# Calliope_mini_rev1_3.net
KiCad netlist of a schematic drawn in EAGLE
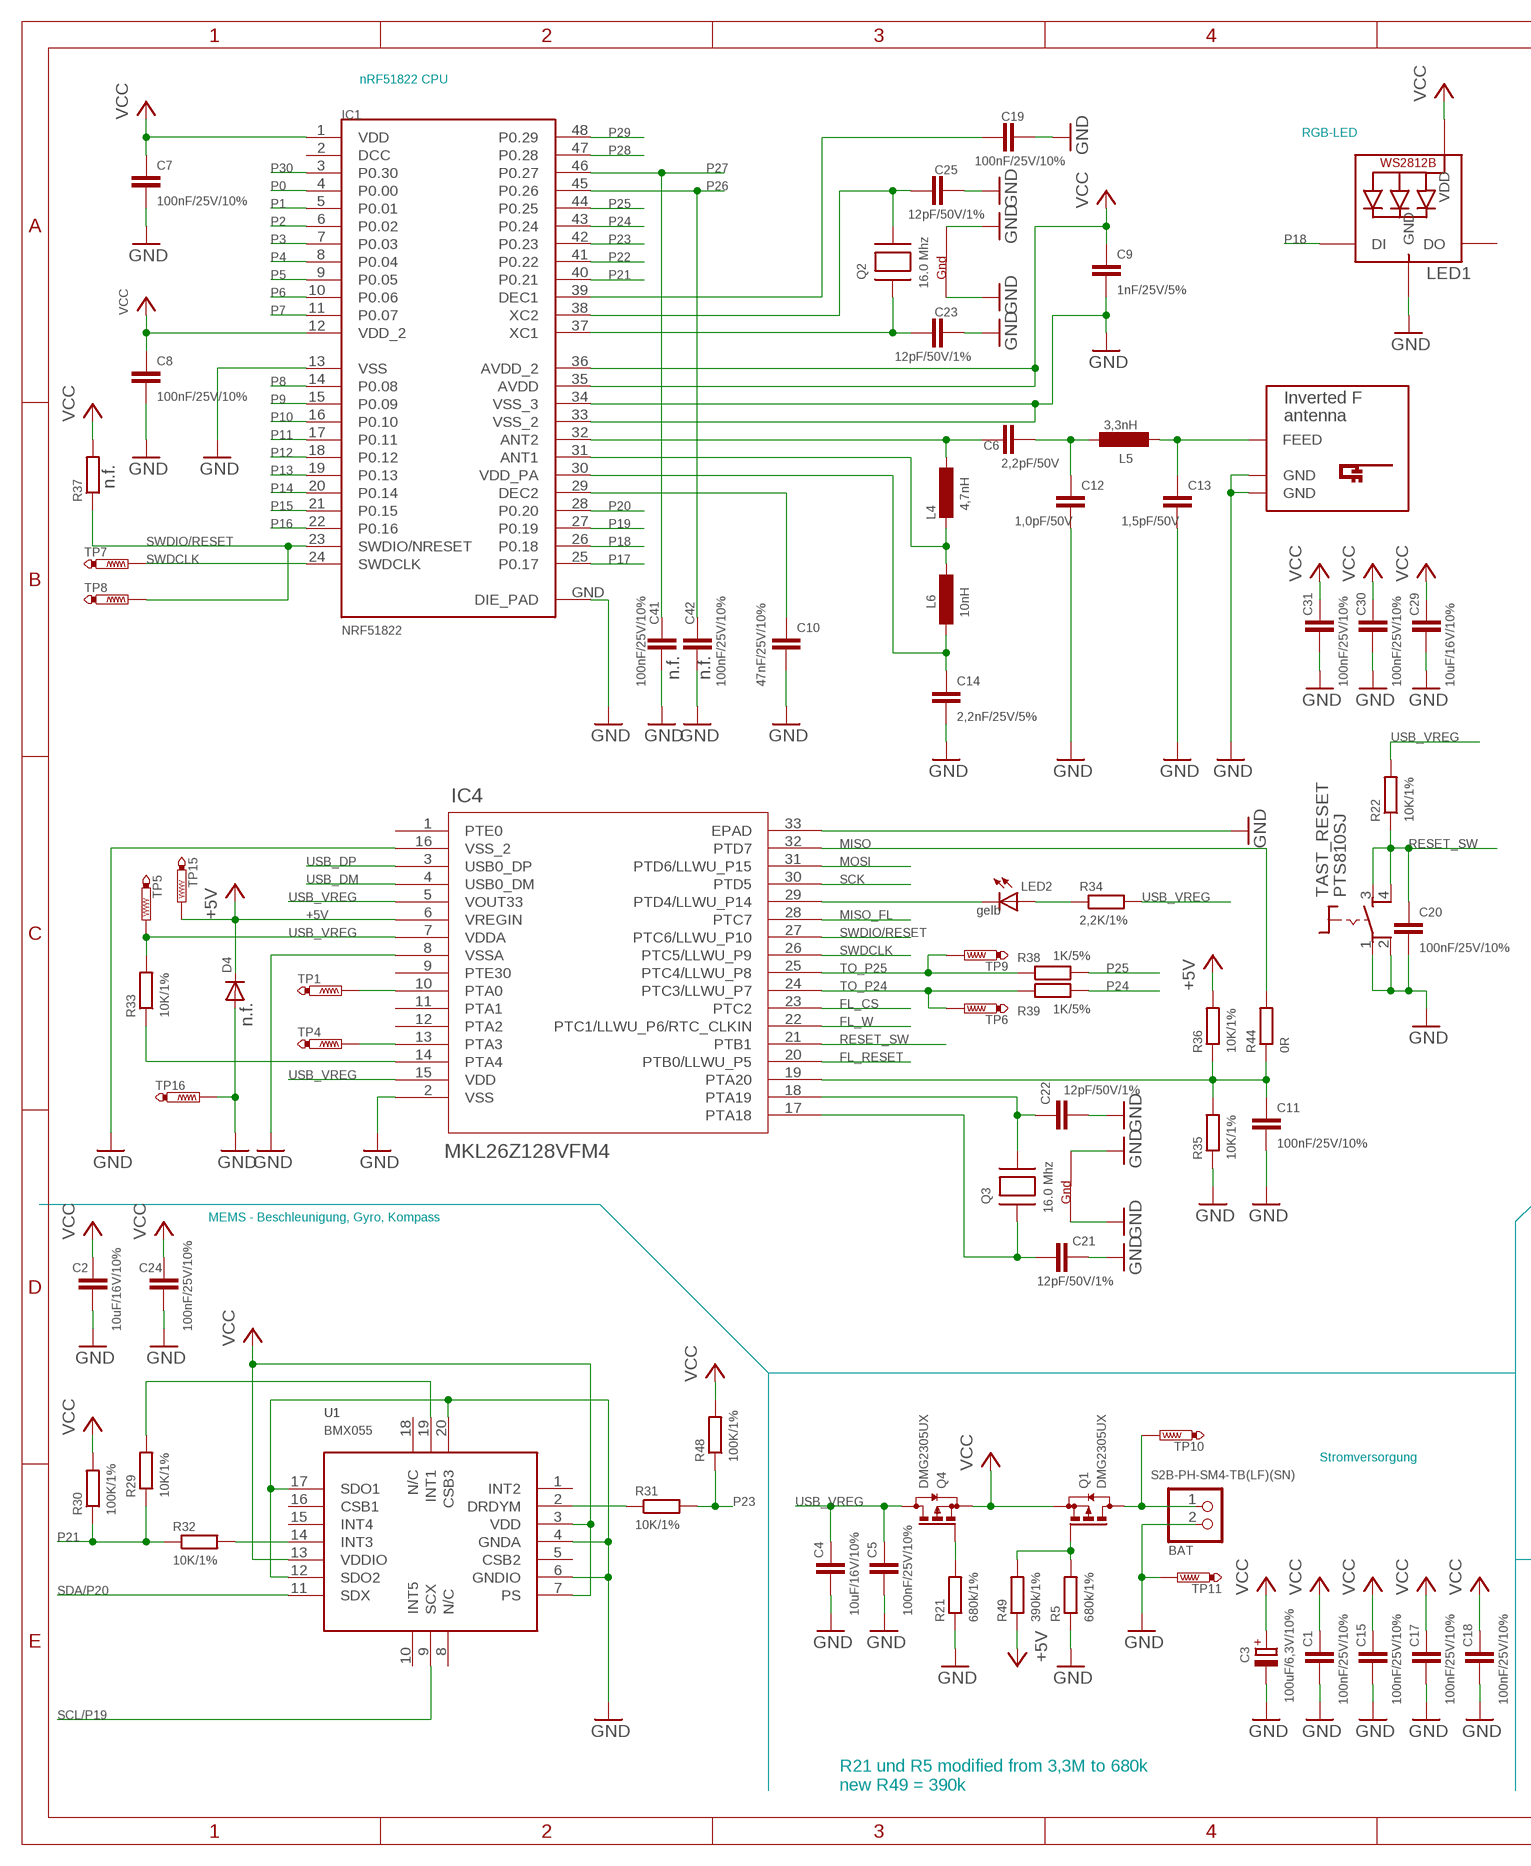
[diagram p0: schematic, sheet 1, part 1 of 2]
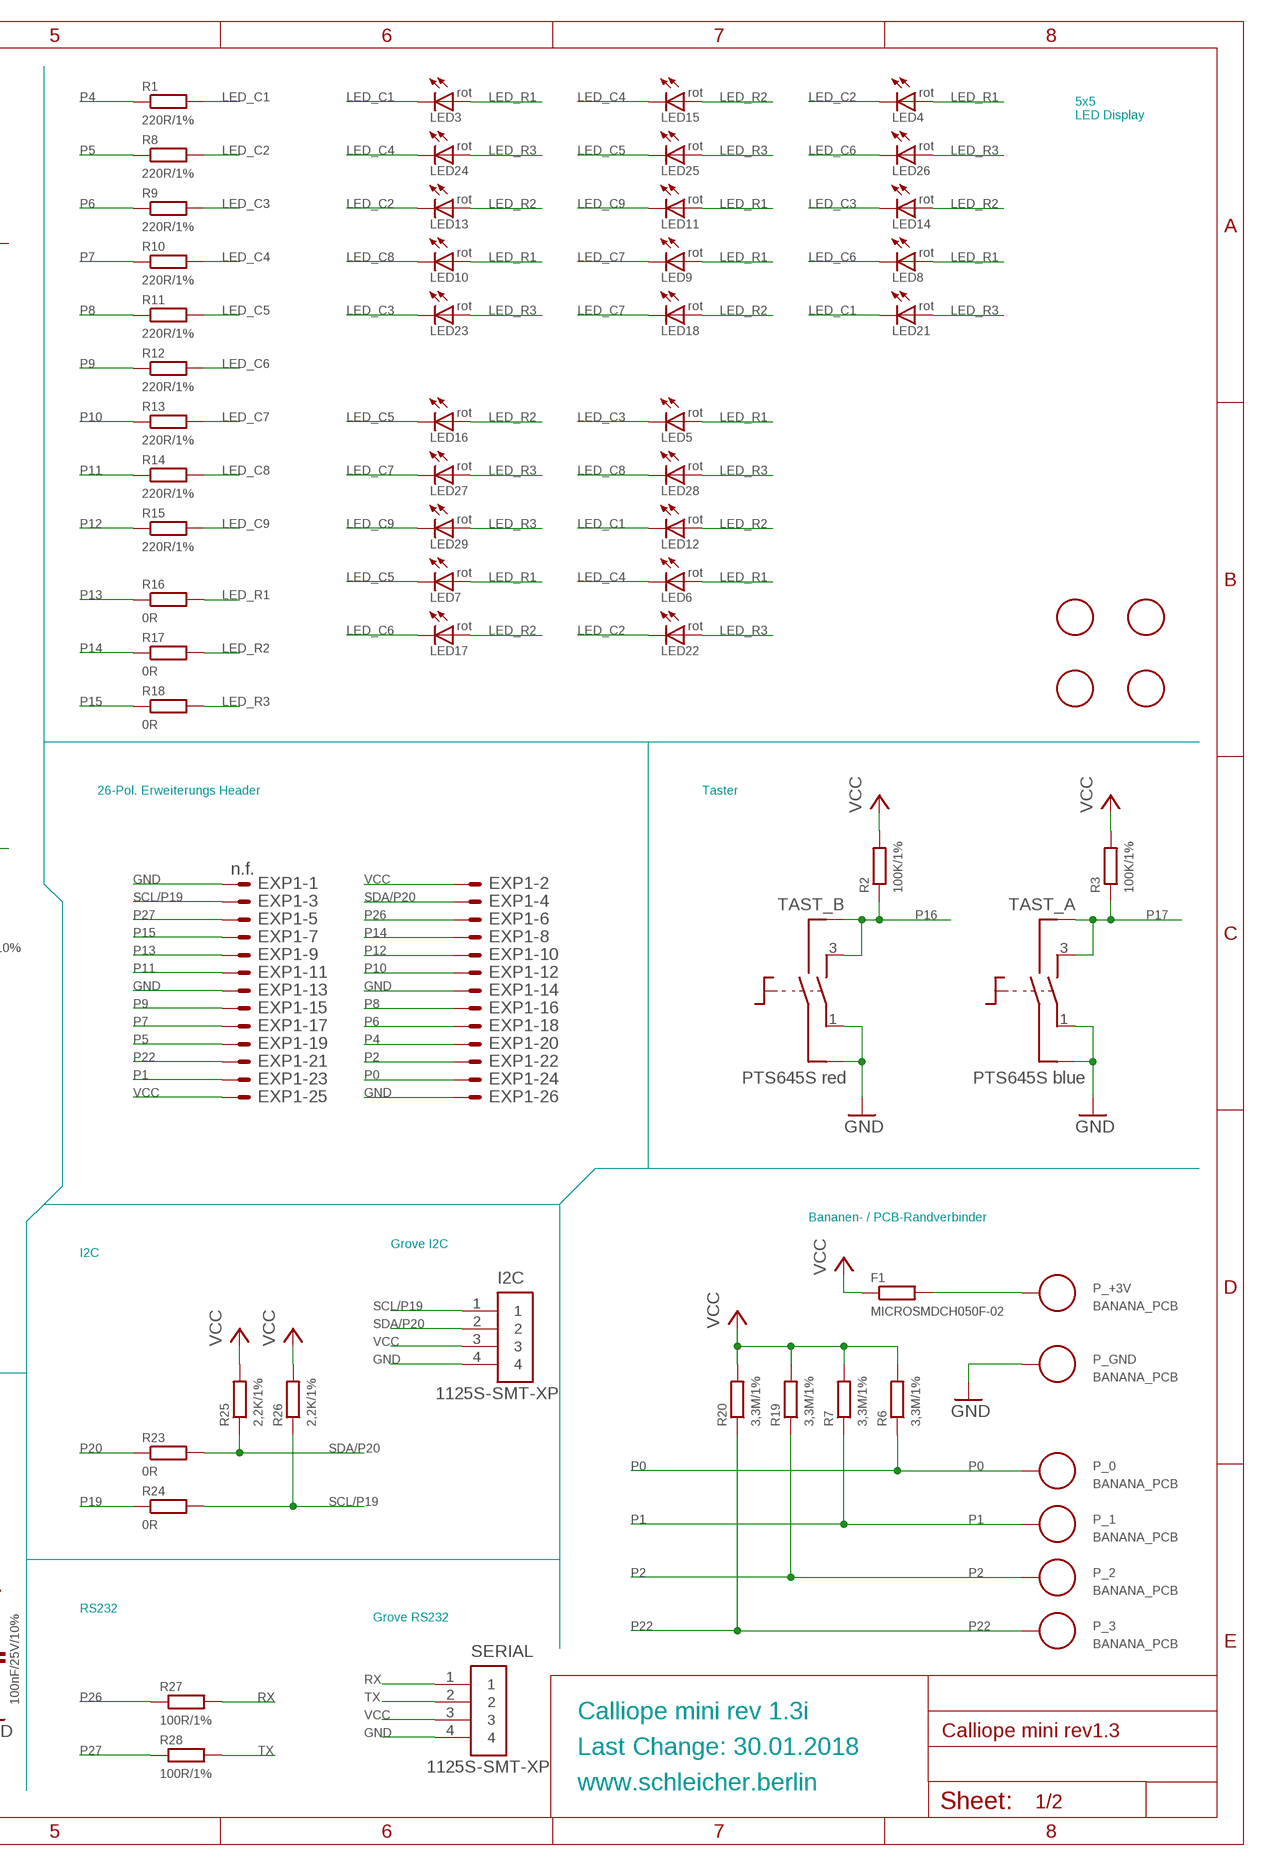
[diagram p1: schematic, sheet 1, part 2 of 2]
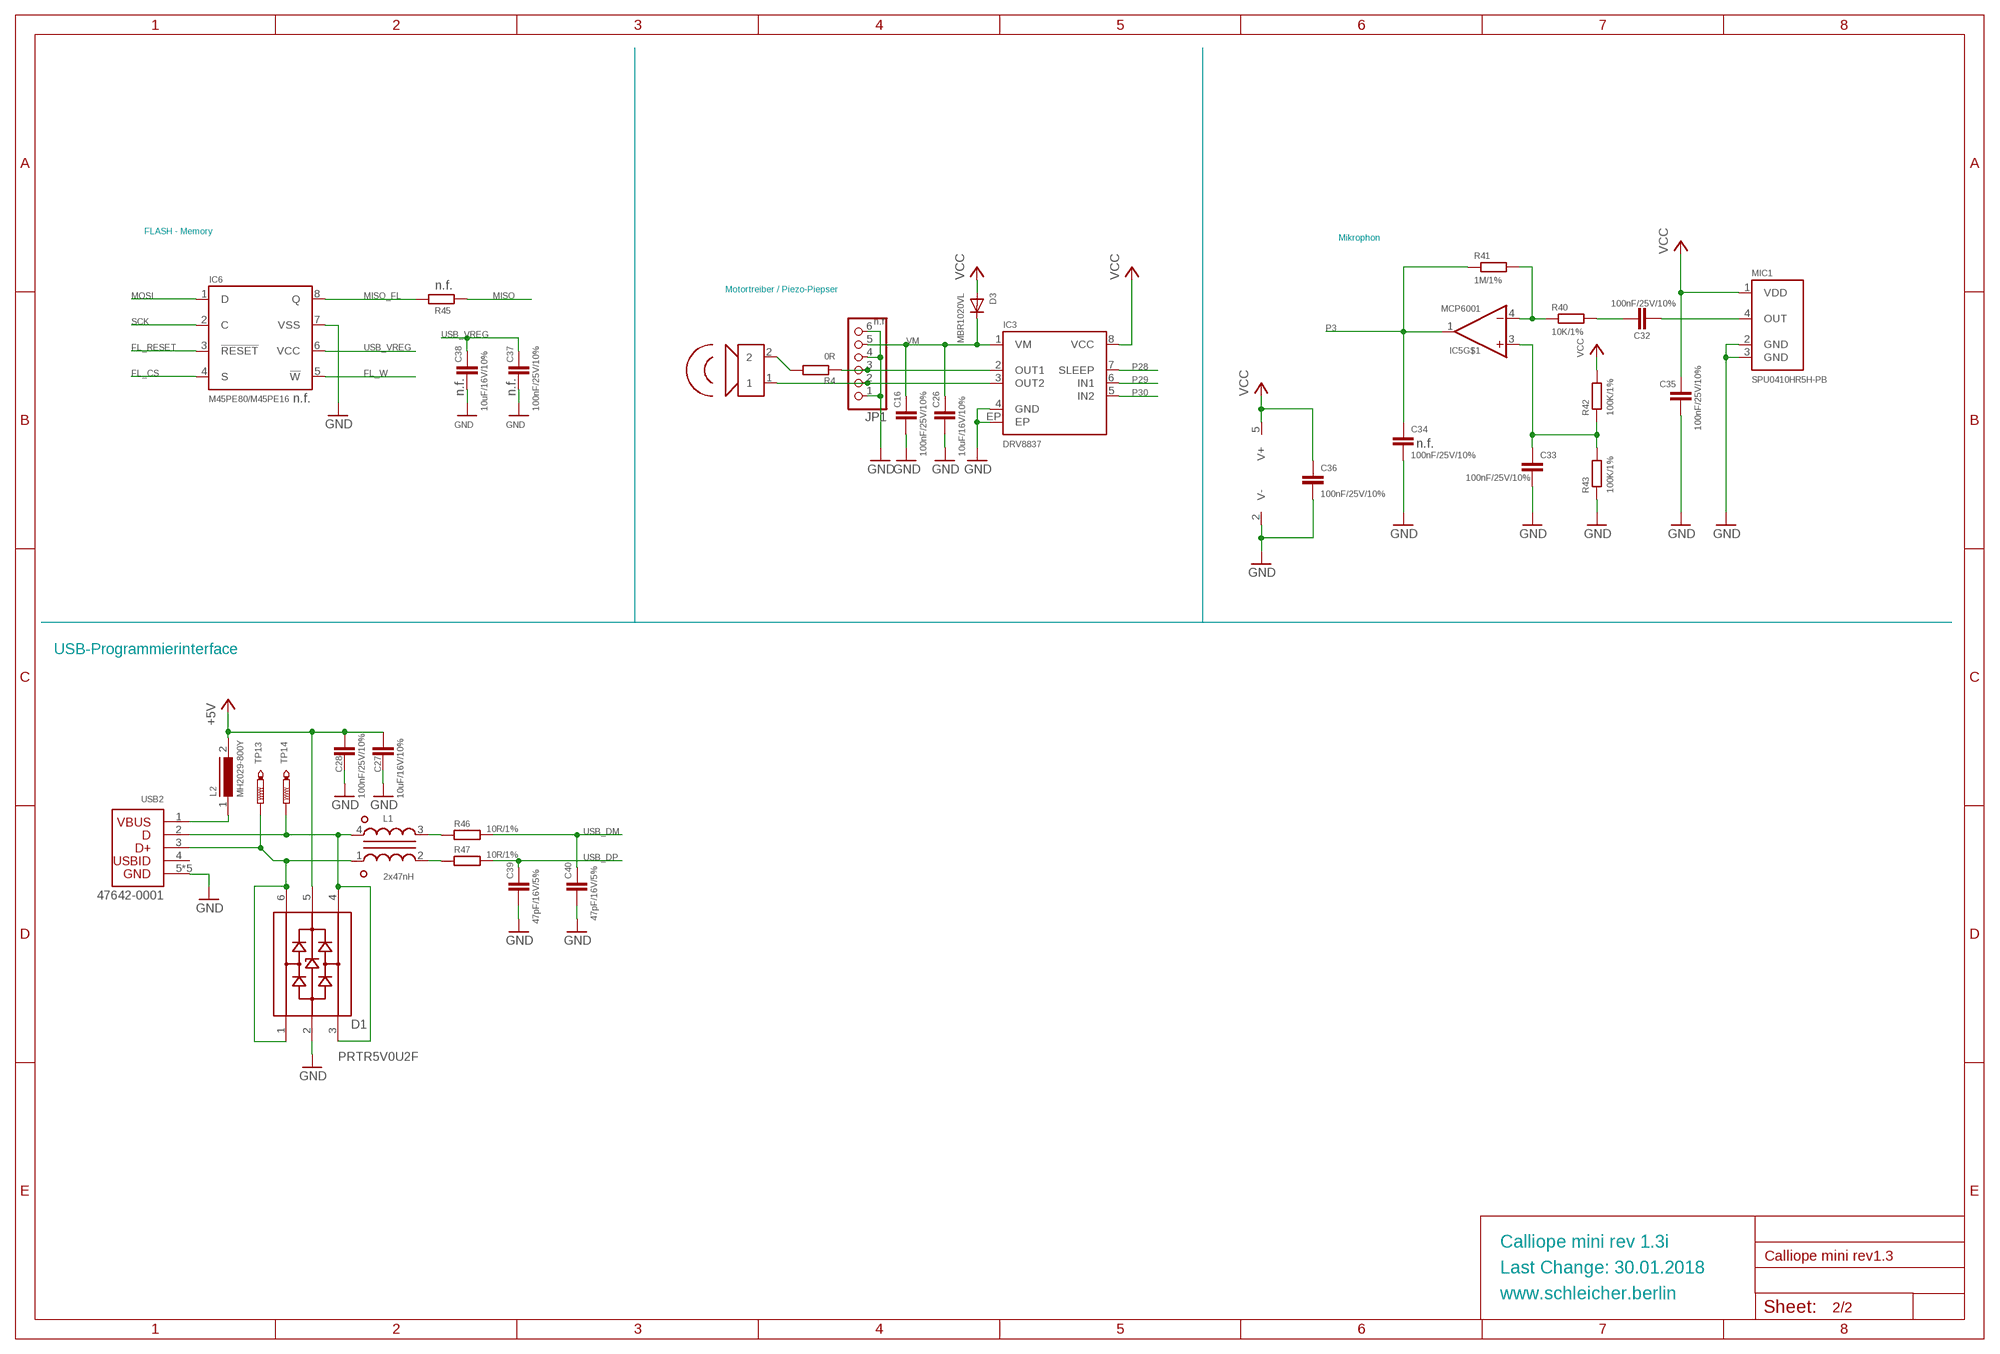
[diagram p2: schematic, sheet 2]

(export (version "E")
  (design (tool "Eeschema 10.0.6"))
  (components
    (comp (ref "BAT")
      (value "S2B-PH-SM4-TB(LF)(SN)")
      (footprint "eagle-import:JST-PH-2-SMT-RA")
      (libsource (lib "eagle-import") (part "JST_2PIN-SMT-RA"))
    )
    (comp (ref "C1")
      (value "100nF/25V/10%")
      (footprint "eagle-import:0402")
      (libsource (lib "eagle-import") (part "C-EU0402"))
    )
    (comp (ref "C2")
      (value "10uF/16V/10%")
      (footprint "eagle-import:0603")
      (libsource (lib "eagle-import") (part "C-EU0603"))
    )
    (comp (ref "C3")
      (value "100uF/6,3V/10%")
      (footprint "eagle-import:D_7343-31R")
      (libsource (lib "eagle-import") (part "CPOL-EUD/7343-31R"))
    )
    (comp (ref "C4")
      (value "10uF/16V/10%")
      (footprint "eagle-import:0603")
      (libsource (lib "eagle-import") (part "C-EU0603"))
    )
    (comp (ref "C5")
      (value "100nF/25V/10%")
      (footprint "eagle-import:0402")
      (libsource (lib "eagle-import") (part "C-EU0402"))
    )
    (comp (ref "C6")
      (value "2,2pF/50V")
      (footprint "eagle-import:0402")
      (libsource (lib "eagle-import") (part "C-EU0402"))
    )
    (comp (ref "C7")
      (value "100nF/25V/10%")
      (footprint "eagle-import:0402")
      (libsource (lib "eagle-import") (part "C-EU0402"))
    )
    (comp (ref "C8")
      (value "100nF/25V/10%")
      (footprint "eagle-import:0402")
      (libsource (lib "eagle-import") (part "C-EU0402"))
    )
    (comp (ref "C9")
      (value "1nF/25V/5%")
      (footprint "eagle-import:0402")
      (libsource (lib "eagle-import") (part "C-EU0402"))
    )
    (comp (ref "C10")
      (value "47nF/25V/10%")
      (footprint "eagle-import:0402")
      (libsource (lib "eagle-import") (part "C-EU0402"))
    )
    (comp (ref "C11")
      (value "100nF/25V/10%")
      (footprint "eagle-import:0402")
      (libsource (lib "eagle-import") (part "C-EU0402"))
    )
    (comp (ref "C12")
      (value "1,0pF/50V")
      (footprint "eagle-import:0402")
      (libsource (lib "eagle-import") (part "C-EU0402"))
    )
    (comp (ref "C13")
      (value "1,5pF/50V")
      (footprint "eagle-import:0402")
      (libsource (lib "eagle-import") (part "C-EU0402"))
    )
    (comp (ref "C14")
      (value "2,2nF/25V/5%")
      (footprint "eagle-import:0402")
      (libsource (lib "eagle-import") (part "C-EU0402"))
    )
    (comp (ref "C15")
      (value "100nF/25V/10%")
      (footprint "eagle-import:0402")
      (libsource (lib "eagle-import") (part "C-EU0402"))
    )
    (comp (ref "C17")
      (value "100nF/25V/10%")
      (footprint "eagle-import:0402")
      (libsource (lib "eagle-import") (part "C-EU0402"))
    )
    (comp (ref "C18")
      (value "100nF/25V/10%")
      (footprint "eagle-import:0402")
      (libsource (lib "eagle-import") (part "C-EU0402"))
    )
    (comp (ref "C19")
      (value "100nF/25V/10%")
      (footprint "eagle-import:0402")
      (libsource (lib "eagle-import") (part "C-EU0402"))
    )
    (comp (ref "C20")
      (value "100nF/25V/10%")
      (footprint "eagle-import:0402")
      (libsource (lib "eagle-import") (part "C-EU0402"))
    )
    (comp (ref "C21")
      (value "12pF/50V/1%")
      (footprint "eagle-import:0402")
      (libsource (lib "eagle-import") (part "C-EU0402"))
    )
    (comp (ref "C22")
      (value "12pF/50V/1%")
      (footprint "eagle-import:0402")
      (libsource (lib "eagle-import") (part "C-EU0402"))
    )
    (comp (ref "C23")
      (value "12pF/50V/1%")
      (footprint "eagle-import:0402")
      (libsource (lib "eagle-import") (part "C-EU0402"))
    )
    (comp (ref "C24")
      (value "100nF/25V/10%")
      (footprint "eagle-import:0402")
      (libsource (lib "eagle-import") (part "C-EU0402"))
    )
    (comp (ref "C25")
      (value "12pF/50V/1%")
      (footprint "eagle-import:0402")
      (libsource (lib "eagle-import") (part "C-EU0402"))
    )
    (comp (ref "C29")
      (value "10uF/16V/10%")
      (footprint "eagle-import:0603")
      (libsource (lib "eagle-import") (part "C-EU0603"))
    )
    (comp (ref "C30")
      (value "100nF/25V/10%")
      (footprint "eagle-import:0402")
      (libsource (lib "eagle-import") (part "C-EU0402"))
    )
    (comp (ref "C31")
      (value "100nF/25V/10%")
      (footprint "eagle-import:0402")
      (libsource (lib "eagle-import") (part "C-EU0402"))
    )
    (comp (ref "C41")
      (value "100nF/25V/10%")
      (footprint "eagle-import:0402")
      (fields (field (name "MOUNTING") "n.f."))
      (libsource (lib "eagle-import") (part "C-EU0402"))
    )
    (comp (ref "C42")
      (value "100nF/25V/10%")
      (footprint "eagle-import:0402")
      (fields (field (name "MOUNTING") "n.f."))
      (libsource (lib "eagle-import") (part "C-EU0402"))
    )
    (comp (ref "D4")
      (value "DIODE-SOD323-R")
      (footprint "eagle-import:SOD323-R")
      (fields (field (name "MOUNTING") "n.f."))
      (libsource (lib "eagle-import") (part "DIODE-SOD323-R"))
    )
    (comp (ref "EXP1")
      (value "ML26E")
      (footprint "eagle-import:ML26")
      (fields (field (name "MOUNTING") "n.f."))
      (libsource (lib "eagle-import") (part "ML26?E"))
    )
    (comp (ref "F1")
      (value "MICROSMDCH050F-02")
      (footprint "eagle-import:R1210")
      (libsource (lib "eagle-import") (part "R-EU_R1210"))
    )
    (comp (ref "I2C")
      (value "1125S-SMT-XP")
      (footprint "eagle-import:1125S-SMT-XP")
      (libsource (lib "eagle-import") (part "1125-SMT-XPS"))
    )
    (comp (ref "IC1")
      (value "NRF51822")
      (footprint "eagle-import:QFN48")
      (libsource (lib "eagle-import") (part "NRF51822"))
    )
    (comp (ref "IC4")
      (value "MKL26Z128VFM4")
      (footprint "eagle-import:QFN_32_5X5X0P9")
      (libsource (lib "eagle-import") (part "MKL26Z"))
    )
    (comp (ref "L4")
      (value "4,7nH")
      (footprint "eagle-import:0402")
      (libsource (lib "eagle-import") (part "L-EU0402"))
    )
    (comp (ref "L5")
      (value "3,3nH")
      (footprint "eagle-import:0402")
      (libsource (lib "eagle-import") (part "L-EU0402"))
    )
    (comp (ref "L6")
      (value "10nH")
      (footprint "eagle-import:0402")
      (libsource (lib "eagle-import") (part "L-EU0402"))
    )
    (comp (ref "LED1")
      (value "SK6812MINI")
      (footprint "eagle-import:LED3535")
      (libsource (lib "eagle-import") (part "WS2812B3535"))
    )
    (comp (ref "LED2")
      (value "gelb")
      (footprint "eagle-import:CHIPLED_0603")
      (libsource (lib "eagle-import") (part "LEDCHIPLED_0603"))
    )
    (comp (ref "LED3")
      (value "rot")
      (footprint "eagle-import:CHIPLED_0603")
      (libsource (lib "eagle-import") (part "LEDCHIPLED_0603"))
    )
    (comp (ref "LED4")
      (value "rot")
      (footprint "eagle-import:CHIPLED_0603")
      (libsource (lib "eagle-import") (part "LEDCHIPLED_0603"))
    )
    (comp (ref "LED5")
      (value "rot")
      (footprint "eagle-import:CHIPLED_0603")
      (libsource (lib "eagle-import") (part "LEDCHIPLED_0603"))
    )
    (comp (ref "LED6")
      (value "rot")
      (footprint "eagle-import:CHIPLED_0603")
      (libsource (lib "eagle-import") (part "LEDCHIPLED_0603"))
    )
    (comp (ref "LED7")
      (value "rot")
      (footprint "eagle-import:CHIPLED_0603")
      (libsource (lib "eagle-import") (part "LEDCHIPLED_0603"))
    )
    (comp (ref "LED8")
      (value "rot")
      (footprint "eagle-import:CHIPLED_0603")
      (libsource (lib "eagle-import") (part "LEDCHIPLED_0603"))
    )
    (comp (ref "LED9")
      (value "rot")
      (footprint "eagle-import:CHIPLED_0603")
      (libsource (lib "eagle-import") (part "LEDCHIPLED_0603"))
    )
    (comp (ref "LED10")
      (value "rot")
      (footprint "eagle-import:CHIPLED_0603")
      (libsource (lib "eagle-import") (part "LEDCHIPLED_0603"))
    )
    (comp (ref "LED11")
      (value "rot")
      (footprint "eagle-import:CHIPLED_0603")
      (libsource (lib "eagle-import") (part "LEDCHIPLED_0603"))
    )
    (comp (ref "LED12")
      (value "rot")
      (footprint "eagle-import:CHIPLED_0603")
      (libsource (lib "eagle-import") (part "LEDCHIPLED_0603"))
    )
    (comp (ref "LED13")
      (value "rot")
      (footprint "eagle-import:CHIPLED_0603")
      (libsource (lib "eagle-import") (part "LEDCHIPLED_0603"))
    )
    (comp (ref "LED14")
      (value "rot")
      (footprint "eagle-import:CHIPLED_0603")
      (libsource (lib "eagle-import") (part "LEDCHIPLED_0603"))
    )
    (comp (ref "LED15")
      (value "rot")
      (footprint "eagle-import:CHIPLED_0603")
      (libsource (lib "eagle-import") (part "LEDCHIPLED_0603"))
    )
    (comp (ref "LED16")
      (value "rot")
      (footprint "eagle-import:CHIPLED_0603")
      (libsource (lib "eagle-import") (part "LEDCHIPLED_0603"))
    )
    (comp (ref "LED17")
      (value "rot")
      (footprint "eagle-import:CHIPLED_0603")
      (libsource (lib "eagle-import") (part "LEDCHIPLED_0603"))
    )
    (comp (ref "LED18")
      (value "rot")
      (footprint "eagle-import:CHIPLED_0603")
      (libsource (lib "eagle-import") (part "LEDCHIPLED_0603"))
    )
    (comp (ref "LED21")
      (value "rot")
      (footprint "eagle-import:CHIPLED_0603")
      (libsource (lib "eagle-import") (part "LEDCHIPLED_0603"))
    )
    (comp (ref "LED22")
      (value "rot")
      (footprint "eagle-import:CHIPLED_0603")
      (libsource (lib "eagle-import") (part "LEDCHIPLED_0603"))
    )
    (comp (ref "LED23")
      (value "rot")
      (footprint "eagle-import:CHIPLED_0603")
      (libsource (lib "eagle-import") (part "LEDCHIPLED_0603"))
    )
    (comp (ref "LED24")
      (value "rot")
      (footprint "eagle-import:CHIPLED_0603")
      (libsource (lib "eagle-import") (part "LEDCHIPLED_0603"))
    )
    (comp (ref "LED25")
      (value "rot")
      (footprint "eagle-import:CHIPLED_0603")
      (libsource (lib "eagle-import") (part "LEDCHIPLED_0603"))
    )
    (comp (ref "LED26")
      (value "rot")
      (footprint "eagle-import:CHIPLED_0603")
      (libsource (lib "eagle-import") (part "LEDCHIPLED_0603"))
    )
    (comp (ref "LED27")
      (value "rot")
      (footprint "eagle-import:CHIPLED_0603")
      (libsource (lib "eagle-import") (part "LEDCHIPLED_0603"))
    )
    (comp (ref "LED28")
      (value "rot")
      (footprint "eagle-import:CHIPLED_0603")
      (libsource (lib "eagle-import") (part "LEDCHIPLED_0603"))
    )
    (comp (ref "LED29")
      (value "rot")
      (footprint "eagle-import:CHIPLED_0603")
      (libsource (lib "eagle-import") (part "LEDCHIPLED_0603"))
    )
    (comp (ref "P_+3V")
      (value "BANANA_PCB")
      (footprint "eagle-import:BANANA_REC")
      (libsource (lib "eagle-import") (part "BANANA_PCB"))
    )
    (comp (ref "P_0")
      (value "BANANA_PCB")
      (footprint "eagle-import:BANANA_REC")
      (libsource (lib "eagle-import") (part "BANANA_PCB"))
    )
    (comp (ref "P_1")
      (value "BANANA_PCB")
      (footprint "eagle-import:BANANA_REC")
      (libsource (lib "eagle-import") (part "BANANA_PCB"))
    )
    (comp (ref "P_2")
      (value "BANANA_PCB")
      (footprint "eagle-import:BANANA_REC")
      (libsource (lib "eagle-import") (part "BANANA_PCB"))
    )
    (comp (ref "P_3")
      (value "BANANA_PCB")
      (footprint "eagle-import:BANANA_REC")
      (libsource (lib "eagle-import") (part "BANANA_PCB"))
    )
    (comp (ref "P_GND")
      (value "BANANA_PCB")
      (footprint "eagle-import:BANANA_REC")
      (libsource (lib "eagle-import") (part "BANANA_PCB"))
    )
    (comp (ref "Q1")
      (value "DMG2305UX")
      (footprint "eagle-import:SOT23")
      (libsource (lib "eagle-import") (part "BSS84"))
    )
    (comp (ref "Q2")
      (value "16.0 Mhz")
      (footprint "eagle-import:NX3225")
      (libsource (lib "eagle-import") (part "XTAL-4-3225"))
    )
    (comp (ref "Q3")
      (value "16.0 Mhz")
      (footprint "eagle-import:NX3225")
      (libsource (lib "eagle-import") (part "XTAL-4-3225"))
    )
    (comp (ref "Q4")
      (value "DMG2305UX")
      (footprint "eagle-import:SOT23")
      (libsource (lib "eagle-import") (part "BSS84"))
    )
    (comp (ref "R1")
      (value "220R/1%")
      (footprint "eagle-import:0402")
      (libsource (lib "eagle-import") (part "R-EU_0402"))
    )
    (comp (ref "R2")
      (value "100K/1%")
      (footprint "eagle-import:0402")
      (libsource (lib "eagle-import") (part "R-EU_0402"))
    )
    (comp (ref "R3")
      (value "100K/1%")
      (footprint "eagle-import:0402")
      (libsource (lib "eagle-import") (part "R-EU_0402"))
    )
    (comp (ref "R5")
      (value "680k/1%")
      (footprint "eagle-import:0402")
      (libsource (lib "eagle-import") (part "R-EU_0402"))
    )
    (comp (ref "R6")
      (value "3,3M/1%")
      (footprint "eagle-import:0402")
      (libsource (lib "eagle-import") (part "R-EU_0402"))
    )
    (comp (ref "R7")
      (value "3,3M/1%")
      (footprint "eagle-import:0402")
      (libsource (lib "eagle-import") (part "R-EU_0402"))
    )
    (comp (ref "R8")
      (value "220R/1%")
      (footprint "eagle-import:0402")
      (libsource (lib "eagle-import") (part "R-EU_0402"))
    )
    (comp (ref "R9")
      (value "220R/1%")
      (footprint "eagle-import:0402")
      (libsource (lib "eagle-import") (part "R-EU_0402"))
    )
    (comp (ref "R10")
      (value "220R/1%")
      (footprint "eagle-import:0402")
      (libsource (lib "eagle-import") (part "R-EU_0402"))
    )
    (comp (ref "R11")
      (value "220R/1%")
      (footprint "eagle-import:0402")
      (libsource (lib "eagle-import") (part "R-EU_0402"))
    )
    (comp (ref "R12")
      (value "220R/1%")
      (footprint "eagle-import:0402")
      (libsource (lib "eagle-import") (part "R-EU_0402"))
    )
    (comp (ref "R13")
      (value "220R/1%")
      (footprint "eagle-import:0402")
      (libsource (lib "eagle-import") (part "R-EU_0402"))
    )
    (comp (ref "R14")
      (value "220R/1%")
      (footprint "eagle-import:0402")
      (libsource (lib "eagle-import") (part "R-EU_0402"))
    )
    (comp (ref "R15")
      (value "220R/1%")
      (footprint "eagle-import:0402")
      (libsource (lib "eagle-import") (part "R-EU_0402"))
    )
    (comp (ref "R16")
      (value "0R")
      (footprint "eagle-import:0402")
      (libsource (lib "eagle-import") (part "R-EU_0402"))
    )
    (comp (ref "R17")
      (value "0R")
      (footprint "eagle-import:0402")
      (libsource (lib "eagle-import") (part "R-EU_0402"))
    )
    (comp (ref "R18")
      (value "0R")
      (footprint "eagle-import:0402")
      (libsource (lib "eagle-import") (part "R-EU_0402"))
    )
    (comp (ref "R19")
      (value "3,3M/1%")
      (footprint "eagle-import:0402")
      (libsource (lib "eagle-import") (part "R-EU_0402"))
    )
    (comp (ref "R20")
      (value "3,3M/1%")
      (footprint "eagle-import:0402")
      (libsource (lib "eagle-import") (part "R-EU_0402"))
    )
    (comp (ref "R21")
      (value "680k/1%")
      (footprint "eagle-import:0402")
      (libsource (lib "eagle-import") (part "R-EU_0402"))
    )
    (comp (ref "R22")
      (value "10K/1%")
      (footprint "eagle-import:0402")
      (libsource (lib "eagle-import") (part "R-EU_0402"))
    )
    (comp (ref "R23")
      (value "0R")
      (footprint "eagle-import:0402")
      (libsource (lib "eagle-import") (part "R-EU_0402"))
    )
    (comp (ref "R24")
      (value "0R")
      (footprint "eagle-import:0402")
      (libsource (lib "eagle-import") (part "R-EU_0402"))
    )
    (comp (ref "R25")
      (value "2,2K/1%")
      (footprint "eagle-import:0402")
      (libsource (lib "eagle-import") (part "R-EU_0402"))
    )
    (comp (ref "R26")
      (value "2,2K/1%")
      (footprint "eagle-import:0402")
      (libsource (lib "eagle-import") (part "R-EU_0402"))
    )
    (comp (ref "R27")
      (value "100R/1%")
      (footprint "eagle-import:0402")
      (libsource (lib "eagle-import") (part "R-EU_0402"))
    )
    (comp (ref "R28")
      (value "100R/1%")
      (footprint "eagle-import:0402")
      (libsource (lib "eagle-import") (part "R-EU_0402"))
    )
    (comp (ref "R29")
      (value "10K/1%")
      (footprint "eagle-import:0402")
      (libsource (lib "eagle-import") (part "R-EU_0402"))
    )
    (comp (ref "R30")
      (value "100K/1%")
      (footprint "eagle-import:0402")
      (libsource (lib "eagle-import") (part "R-EU_0402"))
    )
    (comp (ref "R31")
      (value "10K/1%")
      (footprint "eagle-import:0402")
      (libsource (lib "eagle-import") (part "R-EU_0402"))
    )
    (comp (ref "R32")
      (value "10K/1%")
      (footprint "eagle-import:0402")
      (libsource (lib "eagle-import") (part "R-EU_0402"))
    )
    (comp (ref "R33")
      (value "10K/1%")
      (footprint "eagle-import:0402")
      (libsource (lib "eagle-import") (part "R-EU_0402"))
    )
    (comp (ref "R34")
      (value "2,2K/1%")
      (footprint "eagle-import:0402")
      (libsource (lib "eagle-import") (part "R-EU_0402"))
    )
    (comp (ref "R35")
      (value "10K/1%")
      (footprint "eagle-import:0402")
      (libsource (lib "eagle-import") (part "R-EU_0402"))
    )
    (comp (ref "R36")
      (value "10K/1%")
      (footprint "eagle-import:0402")
      (libsource (lib "eagle-import") (part "R-EU_0402"))
    )
    (comp (ref "R37")
      (value "R-EU_0402")
      (footprint "eagle-import:0402")
      (fields (field (name "MOUNTING") "n.f."))
      (libsource (lib "eagle-import") (part "R-EU_0402"))
    )
    (comp (ref "R38")
      (value "1K/5%")
      (footprint "eagle-import:0402")
      (libsource (lib "eagle-import") (part "R-EU_0402"))
    )
    (comp (ref "R39")
      (value "1K/5%")
      (footprint "eagle-import:0402")
      (libsource (lib "eagle-import") (part "R-EU_0402"))
    )
    (comp (ref "R44")
      (value "0R")
      (footprint "eagle-import:0402")
      (libsource (lib "eagle-import") (part "R-EU_0402"))
    )
    (comp (ref "R48")
      (value "100K/1%")
      (footprint "eagle-import:0402")
      (libsource (lib "eagle-import") (part "R-EU_0402"))
    )
    (comp (ref "R49")
      (value "390k/1%")
      (footprint "eagle-import:0402")
      (libsource (lib "eagle-import") (part "R-EU_0402"))
    )
    (comp (ref "SERIAL")
      (value "1125S-SMT-XP")
      (footprint "eagle-import:1125S-SMT-XP")
      (libsource (lib "eagle-import") (part "1125-SMT-XPS"))
    )
    (comp (ref "TAST_A")
      (value "PTS645S blue")
      (footprint "eagle-import:PTS645S")
      (libsource (lib "eagle-import") (part "PTS645S"))
    )
    (comp (ref "TAST_B")
      (value "PTS645S red")
      (footprint "eagle-import:PTS645S")
      (libsource (lib "eagle-import") (part "PTS645S"))
    )
    (comp (ref "TAST_RESET")
      (value "PTS810SJ")
      (footprint "eagle-import:PTS810")
      (libsource (lib "eagle-import") (part "PTS810SJ"))
    )
    (comp (ref "TP1")
      (value "PTR1B1,27")
      (footprint "eagle-import:B1,27")
      (libsource (lib "eagle-import") (part "PTR1B1,27"))
    )
    (comp (ref "TP4")
      (value "PTR1B1,27")
      (footprint "eagle-import:B1,27")
      (libsource (lib "eagle-import") (part "PTR1B1,27"))
    )
    (comp (ref "TP5")
      (value "PTR1B1,27")
      (footprint "eagle-import:B1,27")
      (libsource (lib "eagle-import") (part "PTR1B1,27"))
    )
    (comp (ref "TP6")
      (value "PTR1B1,27")
      (footprint "eagle-import:B1,27")
      (libsource (lib "eagle-import") (part "PTR1B1,27"))
    )
    (comp (ref "TP7")
      (value "PTR1B1,27")
      (footprint "eagle-import:B1,27")
      (libsource (lib "eagle-import") (part "PTR1B1,27"))
    )
    (comp (ref "TP8")
      (value "PTR1B1,27")
      (footprint "eagle-import:B1,27")
      (libsource (lib "eagle-import") (part "PTR1B1,27"))
    )
    (comp (ref "TP9")
      (value "PTR1B1,27")
      (footprint "eagle-import:B1,27")
      (libsource (lib "eagle-import") (part "PTR1B1,27"))
    )
    (comp (ref "TP10")
      (value "PTR1B1,27")
      (footprint "eagle-import:B1,27")
      (libsource (lib "eagle-import") (part "PTR1B1,27"))
    )
    (comp (ref "TP11")
      (value "PTR1B1,27")
      (footprint "eagle-import:B1,27")
      (libsource (lib "eagle-import") (part "PTR1B1,27"))
    )
    (comp (ref "TP15")
      (value "PTR1B1,27")
      (footprint "eagle-import:B1,27")
      (libsource (lib "eagle-import") (part "PTR1B1,27"))
    )
    (comp (ref "TP16")
      (value "PTR1B1,27")
      (footprint "eagle-import:B1,27")
      (libsource (lib "eagle-import") (part "PTR1B1,27"))
    )
    (comp (ref "U$2")
      (value "INVERTED_F_ANTENNA")
      (footprint "eagle-import:DN0007+0_MIRROR")
      (libsource (lib "eagle-import") (part "INVERTED_F_ANTENNA"))
    )
    (comp (ref "U$5")
      (value "FIDUCIAL")
      (footprint "eagle-import:FIDUCIAL_1MM")
      (libsource (lib "eagle-import") (part "FIDUCIAL"))
    )
    (comp (ref "U$6")
      (value "FIDUCIAL")
      (footprint "eagle-import:FIDUCIAL_1MM")
      (libsource (lib "eagle-import") (part "FIDUCIAL"))
    )
    (comp (ref "U$7")
      (value "FIDUCIAL")
      (footprint "eagle-import:FIDUCIAL_1MM")
      (libsource (lib "eagle-import") (part "FIDUCIAL"))
    )
    (comp (ref "U$8")
      (value "FIDUCIAL")
      (footprint "eagle-import:FIDUCIAL_1MM")
      (libsource (lib "eagle-import") (part "FIDUCIAL"))
    )
    (comp (ref "U1")
      (value "BMX055")
      (footprint "eagle-import:BMX055")
      (libsource (lib "eagle-import") (part "BMX055"))
    )
    (comp (ref "C16")
      (value "100nF/25V/10%")
      (footprint "eagle-import:0402")
      (libsource (lib "eagle-import") (part "C-EU0402"))
    )
    (comp (ref "C26")
      (value "10uF/16V/10%")
      (footprint "eagle-import:0603")
      (libsource (lib "eagle-import") (part "C-EU0603"))
    )
    (comp (ref "C27")
      (value "10uF/16V/10%")
      (footprint "eagle-import:0603")
      (libsource (lib "eagle-import") (part "C-EU0603"))
    )
    (comp (ref "C28")
      (value "100nF/25V/10%")
      (footprint "eagle-import:0402")
      (libsource (lib "eagle-import") (part "C-EU0402"))
    )
    (comp (ref "C32")
      (value "100nF/25V/10%")
      (footprint "eagle-import:0402")
      (libsource (lib "eagle-import") (part "C-EU0402"))
    )
    (comp (ref "C33")
      (value "100nF/25V/10%")
      (footprint "eagle-import:0402")
      (libsource (lib "eagle-import") (part "C-EU0402"))
    )
    (comp (ref "C34")
      (value "100nF/25V/10%")
      (footprint "eagle-import:0402")
      (fields (field (name "MOUNTING") "n.f."))
      (libsource (lib "eagle-import") (part "C-EU0402"))
    )
    (comp (ref "C35")
      (value "100nF/25V/10%")
      (footprint "eagle-import:0402")
      (libsource (lib "eagle-import") (part "C-EU0402"))
    )
    (comp (ref "C36")
      (value "100nF/25V/10%")
      (footprint "eagle-import:0402")
      (libsource (lib "eagle-import") (part "C-EU0402"))
    )
    (comp (ref "C37")
      (value "100nF/25V/10%")
      (footprint "eagle-import:0402")
      (fields (field (name "MOUNTING") "n.f."))
      (libsource (lib "eagle-import") (part "C-EU0402"))
    )
    (comp (ref "C38")
      (value "10uF/16V/10%")
      (footprint "eagle-import:0603")
      (fields (field (name "MOUNTING") "n.f."))
      (libsource (lib "eagle-import") (part "C-EU0603"))
    )
    (comp (ref "C39")
      (value "47pF/16V/5%")
      (footprint "eagle-import:0402")
      (libsource (lib "eagle-import") (part "C-EU0402"))
    )
    (comp (ref "C40")
      (value "47pF/16V/5%")
      (footprint "eagle-import:0402")
      (libsource (lib "eagle-import") (part "C-EU0402"))
    )
    (comp (ref "D1")
      (value "PRTR5V0U2F")
      (footprint "eagle-import:SOT886")
      (libsource (lib "eagle-import") (part "PRTR5V0U2F"))
    )
    (comp (ref "D3")
      (value "MBR1020VL")
      (footprint "eagle-import:SOD-123FL")
      (libsource (lib "eagle-import") (part "DIODE_SOD-123FL"))
    )
    (comp (ref "IC3")
      (value "DRV8837")
      (footprint "eagle-import:WSON8")
      (libsource (lib "eagle-import") (part "DRV8837"))
    )
    (comp (ref "IC5")
      (value "MCP6001")
      (footprint "eagle-import:SOT23-5")
      (libsource (lib "eagle-import") (part "OPAMP_SINGLESOT23-5"))
    )
    (comp (ref "IC6")
      (value "M45PE80/M45PE16")
      (footprint "eagle-import:VQFN8_6X5")
      (fields (field (name "MOUNTING") "n.f."))
      (libsource (lib "eagle-import") (part "M45PE"))
    )
    (comp (ref "JP1")
      (value "PINHD-1X6-OFF")
      (footprint "eagle-import:1X06-OFF")
      (libsource (lib "eagle-import") (part "PINHD-1X6-OFF"))
    )
    (comp (ref "L1")
      (value "2x47nH")
      (footprint "eagle-import:USB_2.0_FILTER_0805")
      (libsource (lib "eagle-import") (part "0805USB-901MLC"))
    )
    (comp (ref "L2")
      (value "MH2029-800Y")
      (footprint "eagle-import:FERRIT_0805")
      (fields (field (name "TOLERANCE") "+-25%"))
      (libsource (lib "eagle-import") (part "MH2029-Y800"))
    )
    (comp (ref "MIC1")
      (value "SPU0410HR5H-PB")
      (footprint "eagle-import:SPU0410HR5H-PB")
      (libsource (lib "eagle-import") (part "SPU0410HR5H-PB"))
    )
    (comp (ref "R4")
      (value "0R")
      (footprint "eagle-import:0402")
      (libsource (lib "eagle-import") (part "R-EU_0402"))
    )
    (comp (ref "R40")
      (value "10K/1%")
      (footprint "eagle-import:0402")
      (libsource (lib "eagle-import") (part "R-EU_0402"))
    )
    (comp (ref "R41")
      (value "1M/1%")
      (footprint "eagle-import:0402")
      (libsource (lib "eagle-import") (part "R-EU_0402"))
    )
    (comp (ref "R42")
      (value "100K/1%")
      (footprint "eagle-import:0402")
      (libsource (lib "eagle-import") (part "R-EU_0402"))
    )
    (comp (ref "R43")
      (value "100K/1%")
      (footprint "eagle-import:0402")
      (libsource (lib "eagle-import") (part "R-EU_0402"))
    )
    (comp (ref "R45")
      (value "R-EU_0402")
      (footprint "eagle-import:0402")
      (fields (field (name "MOUNTING") "n.f."))
      (libsource (lib "eagle-import") (part "R-EU_0402"))
    )
    (comp (ref "R46")
      (value "10R/1%")
      (footprint "eagle-import:R0603")
      (libsource (lib "eagle-import") (part "resistor_R-EU_R0603"))
    )
    (comp (ref "R47")
      (value "10R/1%")
      (footprint "eagle-import:R0603")
      (libsource (lib "eagle-import") (part "resistor_R-EU_R0603"))
    )
    (comp (ref "SPK1")
      (value "PKMCS0909E4000-R1")
      (footprint "eagle-import:PKMCS")
      (libsource (lib "eagle-import") (part "PKMCS0909E4000-R1"))
    )
    (comp (ref "TP13")
      (value "PTR1B1,27")
      (footprint "eagle-import:B1,27")
      (libsource (lib "eagle-import") (part "PTR1B1,27"))
    )
    (comp (ref "TP14")
      (value "PTR1B1,27")
      (footprint "eagle-import:B1,27")
      (libsource (lib "eagle-import") (part "PTR1B1,27"))
    )
    (comp (ref "USB2")
      (value "47642-0001")
      (footprint "eagle-import:47642-0001")
      (libsource (lib "eagle-import") (part "47642-0001"))
    )
  )
  (nets
    (net (code "1") (name "+5V") (class "Default")
      (node (ref "C27") (pin "1") (pinfunction "1_1") (pintype "passive"))
      (node (ref "C28") (pin "1") (pinfunction "1_1") (pintype "passive"))
      (node (ref "D1") (pin "5") (pinfunction "5_5") (pintype "bidirectional"))
      (node (ref "D4") (pin "C") (pinfunction "C_C") (pintype "passive"))
      (node (ref "IC4") (pin "6") (pinfunction "VREGIN_6") (pintype "input"))
      (node (ref "L2") (pin "2") (pinfunction "2_2") (pintype "passive"))
      (node (ref "R36") (pin "2") (pinfunction "2_2") (pintype "passive"))
      (node (ref "R49") (pin "1") (pinfunction "1_1") (pintype "passive"))
      (node (ref "TP15") (pin "TP") (pinfunction "TP_TP") (pintype "input"))
    )
    (net (code "2") (name "FL_CS") (class "Default")
      (node (ref "IC4") (pin "23") (pinfunction "PTC2_23") (pintype "bidirectional"))
      (node (ref "IC6") (pin "4") (pinfunction "S_4") (pintype "bidirectional"))
    )
    (net (code "3") (name "FL_RESET") (class "Default")
      (node (ref "IC4") (pin "20") (pinfunction "PTB0/LLWU_P5_20") (pintype "bidirectional"))
      (node (ref "IC6") (pin "3") (pinfunction "~{RESET}_3") (pintype "bidirectional"))
    )
    (net (code "4") (name "FL_W") (class "Default")
      (node (ref "IC4") (pin "22") (pinfunction "PTC1/LLWU_P6/RTC_CLKIN_22") (pintype "bidirectional"))
      (node (ref "IC6") (pin "5") (pinfunction "~{W}_5") (pintype "bidirectional"))
    )
    (net (code "5") (name "GND") (class "Default")
      (node (ref "BAT") (pin "2") (pinfunction "1_2") (pintype "passive"))
      (node (ref "C1") (pin "2") (pinfunction "2_2") (pintype "passive"))
      (node (ref "C10") (pin "2") (pinfunction "2_2") (pintype "passive"))
      (node (ref "C11") (pin "2") (pinfunction "2_2") (pintype "passive"))
      (node (ref "C12") (pin "2") (pinfunction "2_2") (pintype "passive"))
      (node (ref "C13") (pin "2") (pinfunction "2_2") (pintype "passive"))
      (node (ref "C14") (pin "2") (pinfunction "2_2") (pintype "passive"))
      (node (ref "C15") (pin "2") (pinfunction "2_2") (pintype "passive"))
      (node (ref "C16") (pin "2") (pinfunction "2_2") (pintype "passive"))
      (node (ref "C17") (pin "2") (pinfunction "2_2") (pintype "passive"))
      (node (ref "C18") (pin "2") (pinfunction "2_2") (pintype "passive"))
      (node (ref "C19") (pin "2") (pinfunction "2_2") (pintype "passive"))
      (node (ref "C2") (pin "2") (pinfunction "2_2") (pintype "passive"))
      (node (ref "C20") (pin "2") (pinfunction "2_2") (pintype "passive"))
      (node (ref "C21") (pin "2") (pinfunction "2_2") (pintype "passive"))
      (node (ref "C22") (pin "2") (pinfunction "2_2") (pintype "passive"))
      (node (ref "C23") (pin "2") (pinfunction "2_2") (pintype "passive"))
      (node (ref "C24") (pin "2") (pinfunction "2_2") (pintype "passive"))
      (node (ref "C25") (pin "2") (pinfunction "2_2") (pintype "passive"))
      (node (ref "C26") (pin "2") (pinfunction "2_2") (pintype "passive"))
      (node (ref "C27") (pin "2") (pinfunction "2_2") (pintype "passive"))
      (node (ref "C28") (pin "2") (pinfunction "2_2") (pintype "passive"))
      (node (ref "C29") (pin "2") (pinfunction "2_2") (pintype "passive"))
      (node (ref "C3") (pin "-") (pinfunction "-_-") (pintype "passive"))
      (node (ref "C30") (pin "2") (pinfunction "2_2") (pintype "passive"))
      (node (ref "C31") (pin "2") (pinfunction "2_2") (pintype "passive"))
      (node (ref "C33") (pin "2") (pinfunction "2_2") (pintype "passive"))
      (node (ref "C34") (pin "2") (pinfunction "2_2") (pintype "passive"))
      (node (ref "C35") (pin "2") (pinfunction "2_2") (pintype "passive"))
      (node (ref "C36") (pin "2") (pinfunction "2_2") (pintype "passive"))
      (node (ref "C37") (pin "2") (pinfunction "2_2") (pintype "passive"))
      (node (ref "C38") (pin "2") (pinfunction "2_2") (pintype "passive"))
      (node (ref "C39") (pin "2") (pinfunction "2_2") (pintype "passive"))
      (node (ref "C4") (pin "2") (pinfunction "2_2") (pintype "passive"))
      (node (ref "C40") (pin "2") (pinfunction "2_2") (pintype "passive"))
      (node (ref "C41") (pin "2") (pinfunction "2_2") (pintype "passive"))
      (node (ref "C42") (pin "2") (pinfunction "2_2") (pintype "passive"))
      (node (ref "C5") (pin "2") (pinfunction "2_2") (pintype "passive"))
      (node (ref "C7") (pin "2") (pinfunction "2_2") (pintype "passive"))
      (node (ref "C8") (pin "2") (pinfunction "2_2") (pintype "passive"))
      (node (ref "C9") (pin "2") (pinfunction "2_2") (pintype "passive"))
      (node (ref "D1") (pin "2") (pinfunction "2_2") (pintype "bidirectional"))
      (node (ref "D4") (pin "A") (pinfunction "A_A") (pintype "passive"))
      (node (ref "EXP1") (pin "1") (pinfunction "S_1") (pintype "passive"))
      (node (ref "EXP1") (pin "13") (pinfunction "S_13") (pintype "passive"))
      (node (ref "EXP1") (pin "14") (pinfunction "S_14") (pintype "passive"))
      (node (ref "EXP1") (pin "26") (pinfunction "S_26") (pintype "passive"))
      (node (ref "I2C") (pin "4") (pinfunction "4_4") (pintype "bidirectional"))
      (node (ref "IC1") (pin "13") (pinfunction "VSS_13") (pintype "bidirectional"))
      (node (ref "IC1") (pin "33") (pinfunction "VSS_2_33") (pintype "bidirectional"))
      (node (ref "IC1") (pin "34") (pinfunction "VSS_3_34") (pintype "bidirectional"))
      (node (ref "IC1") (pin "GND") (pinfunction "DIE_PAD_GND") (pintype "bidirectional"))
      (node (ref "IC3") (pin "4") (pinfunction "GND_4") (pintype "bidirectional"))
      (node (ref "IC3") (pin "EP") (pinfunction "EP_EP") (pintype "bidirectional"))
      (node (ref "IC4") (pin "16") (pinfunction "VSS_2_16") (pintype "power_in"))
      (node (ref "IC4") (pin "2") (pinfunction "VSS_2") (pintype "power_in"))
      (node (ref "IC4") (pin "33") (pinfunction "EPAD_33") (pintype "passive"))
      (node (ref "IC4") (pin "8") (pinfunction "VSSA_8") (pintype "power_in"))
      (node (ref "IC5") (pin "2") (pinfunction "V-_2") (pintype "power_in"))
      (node (ref "IC6") (pin "7") (pinfunction "VSS_7") (pintype "bidirectional"))
      (node (ref "JP1") (pin "1") (pinfunction "1_1") (pintype "passive"))
      (node (ref "JP1") (pin "4") (pinfunction "4_4") (pintype "passive"))
      (node (ref "JP1") (pin "6") (pinfunction "6_6") (pintype "passive"))
      (node (ref "LED1") (pin "4") (pinfunction "GND_4") (pintype "power_in"))
      (node (ref "MIC1") (pin "2") (pinfunction "GND_2") (pintype "bidirectional"))
      (node (ref "MIC1") (pin "3") (pinfunction "GND_3") (pintype "bidirectional"))
      (node (ref "P_GND") (pin "1") (pinfunction "1_1") (pintype "bidirectional"))
      (node (ref "Q2") (pin "2") (pinfunction "G2_2") (pintype "power_in"))
      (node (ref "Q2") (pin "4") (pinfunction "G1_4") (pintype "power_in"))
      (node (ref "Q3") (pin "2") (pinfunction "G2_2") (pintype "power_in"))
      (node (ref "Q3") (pin "4") (pinfunction "G1_4") (pintype "power_in"))
      (node (ref "R21") (pin "1") (pinfunction "1_1") (pintype "passive"))
      (node (ref "R35") (pin "1") (pinfunction "1_1") (pintype "passive"))
      (node (ref "R43") (pin "1") (pinfunction "1_1") (pintype "passive"))
      (node (ref "R5") (pin "1") (pinfunction "1_1") (pintype "passive"))
      (node (ref "SERIAL") (pin "4") (pinfunction "4_4") (pintype "bidirectional"))
      (node (ref "TAST_A") (pin "1") (pinfunction "P1_1") (pintype "passive"))
      (node (ref "TAST_A") (pin "2") (pinfunction "P2_2") (pintype "passive"))
      (node (ref "TAST_B") (pin "1") (pinfunction "P1_1") (pintype "passive"))
      (node (ref "TAST_B") (pin "2") (pinfunction "P2_2") (pintype "passive"))
      (node (ref "TAST_RESET") (pin "1") (pinfunction "P_1") (pintype "passive"))
      (node (ref "TAST_RESET") (pin "2") (pinfunction "P1_2") (pintype "passive"))
      (node (ref "TP11") (pin "TP") (pinfunction "TP_TP") (pintype "input"))
      (node (ref "TP16") (pin "TP") (pinfunction "TP_TP") (pintype "input"))
      (node (ref "U$2") (pin "GND") (pinfunction "GND_GND") (pintype "bidirectional"))
      (node (ref "U$2") (pin "GND@1") (pinfunction "GND_GND@1") (pintype "bidirectional"))
      (node (ref "U1") (pin "12") (pinfunction "SDO2_12") (pintype "bidirectional"))
      (node (ref "U1") (pin "17") (pinfunction "SDO1_17") (pintype "bidirectional"))
      (node (ref "U1") (pin "20") (pinfunction "CSB3_20") (pintype "bidirectional"))
      (node (ref "U1") (pin "4") (pinfunction "GNDA_4") (pintype "bidirectional"))
      (node (ref "U1") (pin "6") (pinfunction "GNDIO_6") (pintype "bidirectional"))
      (node (ref "USB2") (pin "5") (pinfunction "5_5") (pintype "bidirectional"))
      (node (ref "USB2") (pin "P$1") (pinfunction "5_P$1") (pintype "bidirectional"))
      (node (ref "USB2") (pin "P$2") (pinfunction "5_P$2") (pintype "bidirectional"))
      (node (ref "USB2") (pin "P$3") (pinfunction "5_P$3") (pintype "bidirectional"))
      (node (ref "USB2") (pin "P$4") (pinfunction "5_P$4") (pintype "bidirectional"))
    )
    (net (code "6") (name "LED_C1") (class "Default")
      (node (ref "LED12") (pin "A") (pinfunction "A_A") (pintype "passive"))
      (node (ref "LED21") (pin "A") (pinfunction "A_A") (pintype "passive"))
      (node (ref "LED3") (pin "A") (pinfunction "A_A") (pintype "passive"))
      (node (ref "R1") (pin "2") (pinfunction "2_2") (pintype "passive"))
    )
    (net (code "7") (name "LED_C2") (class "Default")
      (node (ref "LED13") (pin "A") (pinfunction "A_A") (pintype "passive"))
      (node (ref "LED22") (pin "A") (pinfunction "A_A") (pintype "passive"))
      (node (ref "LED4") (pin "A") (pinfunction "A_A") (pintype "passive"))
      (node (ref "R8") (pin "2") (pinfunction "2_2") (pintype "passive"))
    )
    (net (code "8") (name "LED_C3") (class "Default")
      (node (ref "LED14") (pin "A") (pinfunction "A_A") (pintype "passive"))
      (node (ref "LED23") (pin "A") (pinfunction "A_A") (pintype "passive"))
      (node (ref "LED5") (pin "A") (pinfunction "A_A") (pintype "passive"))
      (node (ref "R9") (pin "2") (pinfunction "2_2") (pintype "passive"))
    )
    (net (code "9") (name "LED_C4") (class "Default")
      (node (ref "LED15") (pin "A") (pinfunction "A_A") (pintype "passive"))
      (node (ref "LED24") (pin "A") (pinfunction "A_A") (pintype "passive"))
      (node (ref "LED6") (pin "A") (pinfunction "A_A") (pintype "passive"))
      (node (ref "R10") (pin "2") (pinfunction "2_2") (pintype "passive"))
    )
    (net (code "10") (name "LED_C5") (class "Default")
      (node (ref "LED16") (pin "A") (pinfunction "A_A") (pintype "passive"))
      (node (ref "LED25") (pin "A") (pinfunction "A_A") (pintype "passive"))
      (node (ref "LED7") (pin "A") (pinfunction "A_A") (pintype "passive"))
      (node (ref "R11") (pin "2") (pinfunction "2_2") (pintype "passive"))
    )
    (net (code "11") (name "LED_C6") (class "Default")
      (node (ref "LED17") (pin "A") (pinfunction "A_A") (pintype "passive"))
      (node (ref "LED26") (pin "A") (pinfunction "A_A") (pintype "passive"))
      (node (ref "LED8") (pin "A") (pinfunction "A_A") (pintype "passive"))
      (node (ref "R12") (pin "2") (pinfunction "2_2") (pintype "passive"))
    )
    (net (code "12") (name "LED_C7") (class "Default")
      (node (ref "LED18") (pin "A") (pinfunction "A_A") (pintype "passive"))
      (node (ref "LED27") (pin "A") (pinfunction "A_A") (pintype "passive"))
      (node (ref "LED9") (pin "A") (pinfunction "A_A") (pintype "passive"))
      (node (ref "R13") (pin "2") (pinfunction "2_2") (pintype "passive"))
    )
    (net (code "13") (name "LED_C8") (class "Default")
      (node (ref "LED10") (pin "A") (pinfunction "A_A") (pintype "passive"))
      (node (ref "LED28") (pin "A") (pinfunction "A_A") (pintype "passive"))
      (node (ref "R14") (pin "2") (pinfunction "2_2") (pintype "passive"))
    )
    (net (code "14") (name "LED_C9") (class "Default")
      (node (ref "LED11") (pin "A") (pinfunction "A_A") (pintype "passive"))
      (node (ref "LED29") (pin "A") (pinfunction "A_A") (pintype "passive"))
      (node (ref "R15") (pin "2") (pinfunction "2_2") (pintype "passive"))
    )
    (net (code "15") (name "LED_R1") (class "Default")
      (node (ref "LED10") (pin "C") (pinfunction "C_C") (pintype "passive"))
      (node (ref "LED11") (pin "C") (pinfunction "C_C") (pintype "passive"))
      (node (ref "LED3") (pin "C") (pinfunction "C_C") (pintype "passive"))
      (node (ref "LED4") (pin "C") (pinfunction "C_C") (pintype "passive"))
      (node (ref "LED5") (pin "C") (pinfunction "C_C") (pintype "passive"))
      (node (ref "LED6") (pin "C") (pinfunction "C_C") (pintype "passive"))
      (node (ref "LED7") (pin "C") (pinfunction "C_C") (pintype "passive"))
      (node (ref "LED8") (pin "C") (pinfunction "C_C") (pintype "passive"))
      (node (ref "LED9") (pin "C") (pinfunction "C_C") (pintype "passive"))
      (node (ref "R16") (pin "2") (pinfunction "2_2") (pintype "passive"))
    )
    (net (code "16") (name "LED_R2") (class "Default")
      (node (ref "LED12") (pin "C") (pinfunction "C_C") (pintype "passive"))
      (node (ref "LED13") (pin "C") (pinfunction "C_C") (pintype "passive"))
      (node (ref "LED14") (pin "C") (pinfunction "C_C") (pintype "passive"))
      (node (ref "LED15") (pin "C") (pinfunction "C_C") (pintype "passive"))
      (node (ref "LED16") (pin "C") (pinfunction "C_C") (pintype "passive"))
      (node (ref "LED17") (pin "C") (pinfunction "C_C") (pintype "passive"))
      (node (ref "LED18") (pin "C") (pinfunction "C_C") (pintype "passive"))
      (node (ref "R17") (pin "2") (pinfunction "2_2") (pintype "passive"))
    )
    (net (code "17") (name "LED_R3") (class "Default")
      (node (ref "LED21") (pin "C") (pinfunction "C_C") (pintype "passive"))
      (node (ref "LED22") (pin "C") (pinfunction "C_C") (pintype "passive"))
      (node (ref "LED23") (pin "C") (pinfunction "C_C") (pintype "passive"))
      (node (ref "LED24") (pin "C") (pinfunction "C_C") (pintype "passive"))
      (node (ref "LED25") (pin "C") (pinfunction "C_C") (pintype "passive"))
      (node (ref "LED26") (pin "C") (pinfunction "C_C") (pintype "passive"))
      (node (ref "LED27") (pin "C") (pinfunction "C_C") (pintype "passive"))
      (node (ref "LED28") (pin "C") (pinfunction "C_C") (pintype "passive"))
      (node (ref "LED29") (pin "C") (pinfunction "C_C") (pintype "passive"))
      (node (ref "R18") (pin "2") (pinfunction "2_2") (pintype "passive"))
    )
    (net (code "18") (name "MISO") (class "Default")
      (node (ref "IC4") (pin "32") (pinfunction "PTD7_32") (pintype "bidirectional"))
      (node (ref "R44") (pin "2") (pinfunction "2_2") (pintype "passive"))
      (node (ref "R45") (pin "1") (pinfunction "1_1") (pintype "passive"))
    )
    (net (code "19") (name "MISO_FL") (class "Default")
      (node (ref "IC4") (pin "28") (pinfunction "PTC7_28") (pintype "bidirectional"))
      (node (ref "IC6") (pin "8") (pinfunction "Q_8") (pintype "bidirectional"))
      (node (ref "R45") (pin "2") (pinfunction "2_2") (pintype "passive"))
    )
    (net (code "20") (name "MOSI") (class "Default")
      (node (ref "IC4") (pin "31") (pinfunction "PTD6/LLWU_P15_31") (pintype "bidirectional"))
      (node (ref "IC6") (pin "1") (pinfunction "D_1") (pintype "bidirectional"))
    )
    (net (code "21") (name "Net-(BAT-2)") (class "Default")
      (node (ref "BAT") (pin "1") (pinfunction "2_1") (pintype "passive"))
      (node (ref "Q1") (pin "3") (pinfunction "D_3") (pintype "passive"))
      (node (ref "TP10") (pin "TP") (pinfunction "TP_TP") (pintype "input"))
    )
    (net (code "22") (name "Net-(C12-Pad1)") (class "Default")
      (node (ref "C12") (pin "1") (pinfunction "1_1") (pintype "passive"))
      (node (ref "C6") (pin "2") (pinfunction "2_2") (pintype "passive"))
      (node (ref "L5") (pin "1") (pinfunction "1_1") (pintype "passive"))
    )
    (net (code "23") (name "Net-(C13-Pad1)") (class "Default")
      (node (ref "C13") (pin "1") (pinfunction "1_1") (pintype "passive"))
      (node (ref "L5") (pin "2") (pinfunction "2_2") (pintype "passive"))
      (node (ref "U$2") (pin "FEED") (pinfunction "FEED_FEED") (pintype "bidirectional"))
    )
    (net (code "24") (name "Net-(C32-Pad1)") (class "Default")
      (node (ref "C32") (pin "1") (pinfunction "1_1") (pintype "passive"))
      (node (ref "R40") (pin "2") (pinfunction "2_2") (pintype "passive"))
    )
    (net (code "25") (name "Net-(D1-Pad1)") (class "Default")
      (node (ref "D1") (pin "1") (pinfunction "1_1") (pintype "bidirectional"))
      (node (ref "D1") (pin "6") (pinfunction "6_6") (pintype "bidirectional"))
      (node (ref "L1") (pin "1") (pinfunction "1_1") (pintype "passive"))
      (node (ref "TP13") (pin "TP") (pinfunction "TP_TP") (pintype "input"))
      (node (ref "USB2") (pin "3") (pinfunction "3_3") (pintype "bidirectional"))
    )
    (net (code "26") (name "Net-(F1-Pad2)") (class "Default")
      (node (ref "F1") (pin "2") (pinfunction "2_2") (pintype "passive"))
      (node (ref "P_+3V") (pin "1") (pinfunction "1_1") (pintype "bidirectional"))
    )
    (net (code "27") (name "Net-(IC1-ANT1)") (class "Default")
      (node (ref "IC1") (pin "31") (pinfunction "ANT1_31") (pintype "bidirectional"))
      (node (ref "L4") (pin "2") (pinfunction "2_2") (pintype "passive"))
      (node (ref "L6") (pin "2") (pinfunction "2_2") (pintype "passive"))
    )
    (net (code "28") (name "Net-(IC1-ANT2)") (class "Default")
      (node (ref "C6") (pin "1") (pinfunction "1_1") (pintype "passive"))
      (node (ref "IC1") (pin "32") (pinfunction "ANT2_32") (pintype "bidirectional"))
      (node (ref "L4") (pin "1") (pinfunction "1_1") (pintype "passive"))
    )
    (net (code "29") (name "Net-(IC1-DEC1)") (class "Default")
      (node (ref "C19") (pin "1") (pinfunction "1_1") (pintype "passive"))
      (node (ref "IC1") (pin "39") (pinfunction "DEC1_39") (pintype "bidirectional"))
    )
    (net (code "30") (name "Net-(IC1-DEC2)") (class "Default")
      (node (ref "C10") (pin "1") (pinfunction "1_1") (pintype "passive"))
      (node (ref "IC1") (pin "29") (pinfunction "DEC2_29") (pintype "bidirectional"))
    )
    (net (code "31") (name "Net-(IC1-VDD_PA)") (class "Default")
      (node (ref "C14") (pin "1") (pinfunction "1_1") (pintype "passive"))
      (node (ref "IC1") (pin "30") (pinfunction "VDD_PA_30") (pintype "bidirectional"))
      (node (ref "L6") (pin "1") (pinfunction "1_1") (pintype "passive"))
    )
    (net (code "32") (name "Net-(IC1-XC1)") (class "Default")
      (node (ref "C23") (pin "1") (pinfunction "1_1") (pintype "passive"))
      (node (ref "IC1") (pin "37") (pinfunction "XC1_37") (pintype "bidirectional"))
      (node (ref "Q2") (pin "1") (pinfunction "X1_1") (pintype "bidirectional"))
    )
    (net (code "33") (name "Net-(IC1-XC2)") (class "Default")
      (node (ref "C25") (pin "1") (pinfunction "1_1") (pintype "passive"))
      (node (ref "IC1") (pin "38") (pinfunction "XC2_38") (pintype "bidirectional"))
      (node (ref "Q2") (pin "3") (pinfunction "X2_3") (pintype "bidirectional"))
    )
    (net (code "34") (name "Net-(IC3-OUT1)") (class "Default")
      (node (ref "IC3") (pin "2") (pinfunction "OUT1_2") (pintype "bidirectional"))
      (node (ref "JP1") (pin "3") (pinfunction "3_3") (pintype "passive"))
      (node (ref "R4") (pin "1") (pinfunction "1_1") (pintype "passive"))
    )
    (net (code "35") (name "Net-(IC3-OUT2)") (class "Default")
      (node (ref "IC3") (pin "3") (pinfunction "OUT2_3") (pintype "bidirectional"))
      (node (ref "JP1") (pin "2") (pinfunction "2_2") (pintype "passive"))
      (node (ref "SPK1") (pin "1") (pinfunction "1_1") (pintype "bidirectional"))
    )
    (net (code "36") (name "Net-(IC4-PTA0)") (class "Default")
      (node (ref "IC4") (pin "10") (pinfunction "PTA0_10") (pintype "bidirectional"))
      (node (ref "TP1") (pin "TP") (pinfunction "TP_TP") (pintype "input"))
    )
    (net (code "37") (name "Net-(IC4-PTA3)") (class "Default")
      (node (ref "IC4") (pin "13") (pinfunction "PTA3_13") (pintype "bidirectional"))
      (node (ref "TP4") (pin "TP") (pinfunction "TP_TP") (pintype "input"))
    )
    (net (code "38") (name "Net-(IC4-PTA4)") (class "Default")
      (node (ref "IC4") (pin "14") (pinfunction "PTA4_14") (pintype "bidirectional"))
      (node (ref "R33") (pin "1") (pinfunction "1_1") (pintype "passive"))
    )
    (net (code "39") (name "Net-(IC4-PTA18)") (class "Default")
      (node (ref "C21") (pin "1") (pinfunction "1_1") (pintype "passive"))
      (node (ref "IC4") (pin "17") (pinfunction "PTA18_17") (pintype "bidirectional"))
      (node (ref "Q3") (pin "1") (pinfunction "X1_1") (pintype "bidirectional"))
    )
    (net (code "40") (name "Net-(IC4-PTA19)") (class "Default")
      (node (ref "C22") (pin "1") (pinfunction "1_1") (pintype "passive"))
      (node (ref "IC4") (pin "18") (pinfunction "PTA19_18") (pintype "bidirectional"))
      (node (ref "Q3") (pin "3") (pinfunction "X2_3") (pintype "bidirectional"))
    )
    (net (code "41") (name "Net-(IC4-PTA20)") (class "Default")
      (node (ref "C11") (pin "1") (pinfunction "1_1") (pintype "passive"))
      (node (ref "IC4") (pin "19") (pinfunction "PTA20_19") (pintype "bidirectional"))
      (node (ref "R35") (pin "2") (pinfunction "2_2") (pintype "passive"))
      (node (ref "R36") (pin "1") (pinfunction "1_1") (pintype "passive"))
      (node (ref "R44") (pin "1") (pinfunction "1_1") (pintype "passive"))
    )
    (net (code "42") (name "Net-(IC4-PTD4{slash}LLWU_P14)") (class "Default")
      (node (ref "IC4") (pin "29") (pinfunction "PTD4/LLWU_P14_29") (pintype "bidirectional"))
      (node (ref "LED2") (pin "A") (pinfunction "A_A") (pintype "passive"))
    )
    (net (code "43") (name "Net-(IC5A-+IN)") (class "Default")
      (node (ref "C33") (pin "1") (pinfunction "1_1") (pintype "passive"))
      (node (ref "IC5") (pin "3") (pinfunction "+IN_3") (pintype "input"))
      (node (ref "R42") (pin "1") (pinfunction "1_1") (pintype "passive"))
      (node (ref "R43") (pin "2") (pinfunction "2_2") (pintype "passive"))
    )
    (net (code "44") (name "Net-(IC5A--IN)") (class "Default")
      (node (ref "IC5") (pin "4") (pinfunction "-IN_4") (pintype "input"))
      (node (ref "R40") (pin "1") (pinfunction "1_1") (pintype "passive"))
      (node (ref "R41") (pin "2") (pinfunction "2_2") (pintype "passive"))
    )
    (net (code "45") (name "Net-(L1-2)") (class "Default")
      (node (ref "D1") (pin "3") (pinfunction "3_3") (pintype "bidirectional"))
      (node (ref "D1") (pin "4") (pinfunction "4_4") (pintype "bidirectional"))
      (node (ref "L1") (pin "4") (pinfunction "2_4") (pintype "passive"))
      (node (ref "TP14") (pin "TP") (pinfunction "TP_TP") (pintype "input"))
      (node (ref "USB2") (pin "2") (pinfunction "2_2") (pintype "bidirectional"))
    )
    (net (code "46") (name "Net-(L1-3)") (class "Default")
      (node (ref "L1") (pin "2") (pinfunction "3_2") (pintype "passive"))
      (node (ref "R47") (pin "1") (pinfunction "1_1") (pintype "passive"))
    )
    (net (code "47") (name "Net-(L1-4)") (class "Default")
      (node (ref "L1") (pin "3") (pinfunction "4_3") (pintype "passive"))
      (node (ref "R46") (pin "1") (pinfunction "1_1") (pintype "passive"))
    )
    (net (code "48") (name "Net-(L2-Pad1)") (class "Default")
      (node (ref "L2") (pin "1") (pinfunction "1_1") (pintype "passive"))
      (node (ref "USB2") (pin "1") (pinfunction "1_1") (pintype "bidirectional"))
    )
    (net (code "49") (name "Net-(LED2-PadC)") (class "Default")
      (node (ref "LED2") (pin "C") (pinfunction "C_C") (pintype "passive"))
      (node (ref "R34") (pin "1") (pinfunction "1_1") (pintype "passive"))
    )
    (net (code "50") (name "Net-(MIC1-OUT)") (class "Default")
      (node (ref "C32") (pin "2") (pinfunction "2_2") (pintype "passive"))
      (node (ref "MIC1") (pin "4") (pinfunction "OUT_4") (pintype "bidirectional"))
    )
    (net (code "51") (name "Net-(Q1-G)") (class "Default")
      (node (ref "Q1") (pin "1") (pinfunction "G_1") (pintype "passive"))
      (node (ref "R49") (pin "2") (pinfunction "2_2") (pintype "passive"))
      (node (ref "R5") (pin "2") (pinfunction "2_2") (pintype "passive"))
    )
    (net (code "52") (name "Net-(Q4-G)") (class "Default")
      (node (ref "Q4") (pin "1") (pinfunction "G_1") (pintype "passive"))
      (node (ref "R21") (pin "2") (pinfunction "2_2") (pintype "passive"))
    )
    (net (code "53") (name "Net-(R4-Pad2)") (class "Default")
      (node (ref "R4") (pin "2") (pinfunction "2_2") (pintype "passive"))
      (node (ref "SPK1") (pin "2") (pinfunction "2_2") (pintype "bidirectional"))
    )
    (net (code "54") (name "Net-(U1-DRDYM)") (class "Default")
      (node (ref "R31") (pin "1") (pinfunction "1_1") (pintype "passive"))
      (node (ref "U1") (pin "2") (pinfunction "DRDYM_2") (pintype "bidirectional"))
    )
    (net (code "55") (name "Net-(U1-INT1)") (class "Default")
      (node (ref "R29") (pin "2") (pinfunction "2_2") (pintype "passive"))
      (node (ref "U1") (pin "19") (pinfunction "INT1_19") (pintype "bidirectional"))
    )
    (net (code "56") (name "Net-(U1-INT3)") (class "Default")
      (node (ref "R32") (pin "2") (pinfunction "2_2") (pintype "passive"))
      (node (ref "U1") (pin "14") (pinfunction "INT3_14") (pintype "bidirectional"))
    )
    (net (code "57") (name "P0") (class "Default")
      (node (ref "EXP1") (pin "24") (pinfunction "S_24") (pintype "passive"))
      (node (ref "IC1") (pin "4") (pinfunction "P0.00_4") (pintype "bidirectional"))
      (node (ref "P_0") (pin "1") (pinfunction "1_1") (pintype "bidirectional"))
      (node (ref "R6") (pin "1") (pinfunction "1_1") (pintype "passive"))
    )
    (net (code "58") (name "P1") (class "Default")
      (node (ref "EXP1") (pin "23") (pinfunction "S_23") (pintype "passive"))
      (node (ref "IC1") (pin "5") (pinfunction "P0.01_5") (pintype "bidirectional"))
      (node (ref "P_1") (pin "1") (pinfunction "1_1") (pintype "bidirectional"))
      (node (ref "R7") (pin "1") (pinfunction "1_1") (pintype "passive"))
    )
    (net (code "59") (name "P2") (class "Default")
      (node (ref "EXP1") (pin "22") (pinfunction "S_22") (pintype "passive"))
      (node (ref "IC1") (pin "6") (pinfunction "P0.02_6") (pintype "bidirectional"))
      (node (ref "P_2") (pin "1") (pinfunction "1_1") (pintype "bidirectional"))
      (node (ref "R19") (pin "1") (pinfunction "1_1") (pintype "passive"))
    )
    (net (code "60") (name "P3") (class "Default")
      (node (ref "C34") (pin "1") (pinfunction "1_1") (pintype "passive"))
      (node (ref "IC1") (pin "7") (pinfunction "P0.03_7") (pintype "bidirectional"))
      (node (ref "IC5") (pin "1") (pinfunction "OUT_1") (pintype "output"))
      (node (ref "R41") (pin "1") (pinfunction "1_1") (pintype "passive"))
    )
    (net (code "61") (name "P4") (class "Default")
      (node (ref "EXP1") (pin "20") (pinfunction "S_20") (pintype "passive"))
      (node (ref "IC1") (pin "8") (pinfunction "P0.04_8") (pintype "bidirectional"))
      (node (ref "R1") (pin "1") (pinfunction "1_1") (pintype "passive"))
    )
    (net (code "62") (name "P5") (class "Default")
      (node (ref "EXP1") (pin "19") (pinfunction "S_19") (pintype "passive"))
      (node (ref "IC1") (pin "9") (pinfunction "P0.05_9") (pintype "bidirectional"))
      (node (ref "R8") (pin "1") (pinfunction "1_1") (pintype "passive"))
    )
    (net (code "63") (name "P6") (class "Default")
      (node (ref "EXP1") (pin "18") (pinfunction "S_18") (pintype "passive"))
      (node (ref "IC1") (pin "10") (pinfunction "P0.06_10") (pintype "bidirectional"))
      (node (ref "R9") (pin "1") (pinfunction "1_1") (pintype "passive"))
    )
    (net (code "64") (name "P7") (class "Default")
      (node (ref "EXP1") (pin "17") (pinfunction "S_17") (pintype "passive"))
      (node (ref "IC1") (pin "11") (pinfunction "P0.07_11") (pintype "bidirectional"))
      (node (ref "R10") (pin "1") (pinfunction "1_1") (pintype "passive"))
    )
    (net (code "65") (name "P8") (class "Default")
      (node (ref "EXP1") (pin "16") (pinfunction "S_16") (pintype "passive"))
      (node (ref "IC1") (pin "14") (pinfunction "P0.08_14") (pintype "bidirectional"))
      (node (ref "R11") (pin "1") (pinfunction "1_1") (pintype "passive"))
    )
    (net (code "66") (name "P9") (class "Default")
      (node (ref "EXP1") (pin "15") (pinfunction "S_15") (pintype "passive"))
      (node (ref "IC1") (pin "15") (pinfunction "P0.09_15") (pintype "bidirectional"))
      (node (ref "R12") (pin "1") (pinfunction "1_1") (pintype "passive"))
    )
    (net (code "67") (name "P10") (class "Default")
      (node (ref "EXP1") (pin "12") (pinfunction "S_12") (pintype "passive"))
      (node (ref "IC1") (pin "16") (pinfunction "P0.10_16") (pintype "bidirectional"))
      (node (ref "R13") (pin "1") (pinfunction "1_1") (pintype "passive"))
    )
    (net (code "68") (name "P11") (class "Default")
      (node (ref "EXP1") (pin "11") (pinfunction "S_11") (pintype "passive"))
      (node (ref "IC1") (pin "17") (pinfunction "P0.11_17") (pintype "bidirectional"))
      (node (ref "R14") (pin "1") (pinfunction "1_1") (pintype "passive"))
    )
    (net (code "69") (name "P12") (class "Default")
      (node (ref "EXP1") (pin "10") (pinfunction "S_10") (pintype "passive"))
      (node (ref "IC1") (pin "18") (pinfunction "P0.12_18") (pintype "bidirectional"))
      (node (ref "R15") (pin "1") (pinfunction "1_1") (pintype "passive"))
    )
    (net (code "70") (name "P13") (class "Default")
      (node (ref "EXP1") (pin "9") (pinfunction "S_9") (pintype "passive"))
      (node (ref "IC1") (pin "19") (pinfunction "P0.13_19") (pintype "bidirectional"))
      (node (ref "R16") (pin "1") (pinfunction "1_1") (pintype "passive"))
    )
    (net (code "71") (name "P14") (class "Default")
      (node (ref "EXP1") (pin "8") (pinfunction "S_8") (pintype "passive"))
      (node (ref "IC1") (pin "20") (pinfunction "P0.14_20") (pintype "bidirectional"))
      (node (ref "R17") (pin "1") (pinfunction "1_1") (pintype "passive"))
    )
    (net (code "72") (name "P15") (class "Default")
      (node (ref "EXP1") (pin "7") (pinfunction "S_7") (pintype "passive"))
      (node (ref "IC1") (pin "21") (pinfunction "P0.15_21") (pintype "bidirectional"))
      (node (ref "R18") (pin "1") (pinfunction "1_1") (pintype "passive"))
    )
    (net (code "73") (name "P16") (class "Default")
      (node (ref "IC1") (pin "22") (pinfunction "P0.16_22") (pintype "bidirectional"))
      (node (ref "R2") (pin "1") (pinfunction "1_1") (pintype "passive"))
      (node (ref "TAST_B") (pin "3") (pinfunction "S1_3") (pintype "passive"))
      (node (ref "TAST_B") (pin "4") (pinfunction "S2_4") (pintype "passive"))
    )
    (net (code "74") (name "P17") (class "Default")
      (node (ref "IC1") (pin "25") (pinfunction "P0.17_25") (pintype "bidirectional"))
      (node (ref "R3") (pin "1") (pinfunction "1_1") (pintype "passive"))
      (node (ref "TAST_A") (pin "3") (pinfunction "S1_3") (pintype "passive"))
      (node (ref "TAST_A") (pin "4") (pinfunction "S2_4") (pintype "passive"))
    )
    (net (code "75") (name "P18") (class "Default")
      (node (ref "IC1") (pin "26") (pinfunction "P0.18_26") (pintype "bidirectional"))
      (node (ref "LED1") (pin "1") (pinfunction "DI_1") (pintype "input"))
    )
    (net (code "76") (name "P19") (class "Default")
      (node (ref "IC1") (pin "27") (pinfunction "P0.19_27") (pintype "bidirectional"))
      (node (ref "R24") (pin "1") (pinfunction "1_1") (pintype "passive"))
    )
    (net (code "77") (name "P20") (class "Default")
      (node (ref "IC1") (pin "28") (pinfunction "P0.20_28") (pintype "bidirectional"))
      (node (ref "R23") (pin "1") (pinfunction "1_1") (pintype "passive"))
    )
    (net (code "78") (name "P21") (class "Default")
      (node (ref "IC1") (pin "40") (pinfunction "P0.21_40") (pintype "bidirectional"))
      (node (ref "R29") (pin "1") (pinfunction "1_1") (pintype "passive"))
      (node (ref "R30") (pin "1") (pinfunction "1_1") (pintype "passive"))
      (node (ref "R32") (pin "1") (pinfunction "1_1") (pintype "passive"))
    )
    (net (code "79") (name "P22") (class "Default")
      (node (ref "EXP1") (pin "21") (pinfunction "S_21") (pintype "passive"))
      (node (ref "IC1") (pin "41") (pinfunction "P0.22_41") (pintype "bidirectional"))
      (node (ref "P_3") (pin "1") (pinfunction "1_1") (pintype "bidirectional"))
      (node (ref "R20") (pin "1") (pinfunction "1_1") (pintype "passive"))
    )
    (net (code "80") (name "P23") (class "Default")
      (node (ref "IC1") (pin "42") (pinfunction "P0.23_42") (pintype "bidirectional"))
      (node (ref "R31") (pin "2") (pinfunction "2_2") (pintype "passive"))
      (node (ref "R48") (pin "1") (pinfunction "1_1") (pintype "passive"))
    )
    (net (code "81") (name "P24") (class "Default")
      (node (ref "IC1") (pin "43") (pinfunction "P0.24_43") (pintype "bidirectional"))
      (node (ref "R39") (pin "2") (pinfunction "2_2") (pintype "passive"))
    )
    (net (code "82") (name "P25") (class "Default")
      (node (ref "IC1") (pin "44") (pinfunction "P0.25_44") (pintype "bidirectional"))
      (node (ref "R38") (pin "2") (pinfunction "2_2") (pintype "passive"))
    )
    (net (code "83") (name "P26") (class "Default")
      (node (ref "C42") (pin "1") (pinfunction "1_1") (pintype "passive"))
      (node (ref "EXP1") (pin "6") (pinfunction "S_6") (pintype "passive"))
      (node (ref "IC1") (pin "45") (pinfunction "P0.26_45") (pintype "bidirectional"))
      (node (ref "R27") (pin "1") (pinfunction "1_1") (pintype "passive"))
    )
    (net (code "84") (name "P27") (class "Default")
      (node (ref "C41") (pin "1") (pinfunction "1_1") (pintype "passive"))
      (node (ref "EXP1") (pin "5") (pinfunction "S_5") (pintype "passive"))
      (node (ref "IC1") (pin "46") (pinfunction "P0.27_46") (pintype "bidirectional"))
      (node (ref "R28") (pin "1") (pinfunction "1_1") (pintype "passive"))
    )
    (net (code "85") (name "P28") (class "Default")
      (node (ref "IC1") (pin "47") (pinfunction "P0.28_47") (pintype "bidirectional"))
      (node (ref "IC3") (pin "7") (pinfunction "SLEEP_7") (pintype "bidirectional"))
    )
    (net (code "86") (name "P29") (class "Default")
      (node (ref "IC1") (pin "48") (pinfunction "P0.29_48") (pintype "bidirectional"))
      (node (ref "IC3") (pin "6") (pinfunction "IN1_6") (pintype "bidirectional"))
    )
    (net (code "87") (name "P30") (class "Default")
      (node (ref "IC1") (pin "3") (pinfunction "P0.30_3") (pintype "bidirectional"))
      (node (ref "IC3") (pin "5") (pinfunction "IN2_5") (pintype "bidirectional"))
    )
    (net (code "88") (name "RESET_SW") (class "Default")
      (node (ref "C20") (pin "1") (pinfunction "1_1") (pintype "passive"))
      (node (ref "IC4") (pin "21") (pinfunction "PTB1_21") (pintype "bidirectional"))
      (node (ref "R22") (pin "1") (pinfunction "1_1") (pintype "passive"))
      (node (ref "TAST_RESET") (pin "3") (pinfunction "S_3") (pintype "passive"))
      (node (ref "TAST_RESET") (pin "4") (pinfunction "S1_4") (pintype "passive"))
    )
    (net (code "89") (name "RX") (class "Default")
      (node (ref "R27") (pin "2") (pinfunction "2_2") (pintype "passive"))
      (node (ref "SERIAL") (pin "1") (pinfunction "1_1") (pintype "bidirectional"))
    )
    (net (code "90") (name "SCK") (class "Default")
      (node (ref "IC4") (pin "30") (pinfunction "PTD5_30") (pintype "bidirectional"))
      (node (ref "IC6") (pin "2") (pinfunction "C_2") (pintype "bidirectional"))
    )
    (net (code "91") (name "SCL{slash}P19") (class "Default")
      (node (ref "EXP1") (pin "3") (pinfunction "S_3") (pintype "passive"))
      (node (ref "I2C") (pin "1") (pinfunction "1_1") (pintype "bidirectional"))
      (node (ref "R24") (pin "2") (pinfunction "2_2") (pintype "passive"))
      (node (ref "R26") (pin "1") (pinfunction "1_1") (pintype "passive"))
      (node (ref "U1") (pin "9") (pinfunction "SCX_9") (pintype "bidirectional"))
    )
    (net (code "92") (name "SDA{slash}P20") (class "Default")
      (node (ref "EXP1") (pin "4") (pinfunction "S_4") (pintype "passive"))
      (node (ref "I2C") (pin "2") (pinfunction "2_2") (pintype "bidirectional"))
      (node (ref "R23") (pin "2") (pinfunction "2_2") (pintype "passive"))
      (node (ref "R25") (pin "1") (pinfunction "1_1") (pintype "passive"))
      (node (ref "U1") (pin "11") (pinfunction "SDX_11") (pintype "bidirectional"))
    )
    (net (code "93") (name "SWDCLK") (class "Default")
      (node (ref "IC1") (pin "24") (pinfunction "SWDCLK_24") (pintype "bidirectional"))
      (node (ref "IC4") (pin "26") (pinfunction "PTC5/LLWU_P9_26") (pintype "bidirectional"))
      (node (ref "TP7") (pin "TP") (pinfunction "TP_TP") (pintype "input"))
    )
    (net (code "94") (name "SWDIO{slash}RESET") (class "Default")
      (node (ref "IC1") (pin "23") (pinfunction "SWDIO/NRESET_23") (pintype "bidirectional"))
      (node (ref "IC4") (pin "27") (pinfunction "PTC6/LLWU_P10_27") (pintype "bidirectional"))
      (node (ref "R37") (pin "1") (pinfunction "1_1") (pintype "passive"))
      (node (ref "TP8") (pin "TP") (pinfunction "TP_TP") (pintype "input"))
    )
    (net (code "95") (name "TO_P24") (class "Default")
      (node (ref "IC4") (pin "24") (pinfunction "PTC3/LLWU_P7_24") (pintype "bidirectional"))
      (node (ref "R39") (pin "1") (pinfunction "1_1") (pintype "passive"))
      (node (ref "TP6") (pin "TP") (pinfunction "TP_TP") (pintype "input"))
    )
    (net (code "96") (name "TO_P25") (class "Default")
      (node (ref "IC4") (pin "25") (pinfunction "PTC4/LLWU_P8_25") (pintype "bidirectional"))
      (node (ref "R38") (pin "1") (pinfunction "1_1") (pintype "passive"))
      (node (ref "TP9") (pin "TP") (pinfunction "TP_TP") (pintype "input"))
    )
    (net (code "97") (name "TX") (class "Default")
      (node (ref "R28") (pin "2") (pinfunction "2_2") (pintype "passive"))
      (node (ref "SERIAL") (pin "2") (pinfunction "2_2") (pintype "bidirectional"))
    )
    (net (code "98") (name "USB_DM") (class "Default")
      (node (ref "C40") (pin "1") (pinfunction "1_1") (pintype "passive"))
      (node (ref "IC4") (pin "4") (pinfunction "USB0_DM_4") (pintype "passive"))
      (node (ref "R46") (pin "2") (pinfunction "2_2") (pintype "passive"))
    )
    (net (code "99") (name "USB_DP") (class "Default")
      (node (ref "C39") (pin "1") (pinfunction "1_1") (pintype "passive"))
      (node (ref "IC4") (pin "3") (pinfunction "USB0_DP_3") (pintype "passive"))
      (node (ref "R47") (pin "2") (pinfunction "2_2") (pintype "passive"))
    )
    (net (code "100") (name "USB_VREG") (class "Default")
      (node (ref "C37") (pin "1") (pinfunction "1_1") (pintype "passive"))
      (node (ref "C38") (pin "1") (pinfunction "1_1") (pintype "passive"))
      (node (ref "C4") (pin "1") (pinfunction "1_1") (pintype "passive"))
      (node (ref "C5") (pin "1") (pinfunction "1_1") (pintype "passive"))
      (node (ref "IC4") (pin "15") (pinfunction "VDD_15") (pintype "power_in"))
      (node (ref "IC4") (pin "5") (pinfunction "VOUT33_5") (pintype "output"))
      (node (ref "IC4") (pin "7") (pinfunction "VDDA_7") (pintype "power_in"))
      (node (ref "IC6") (pin "6") (pinfunction "VCC_6") (pintype "bidirectional"))
      (node (ref "Q4") (pin "3") (pinfunction "D_3") (pintype "passive"))
      (node (ref "R22") (pin "2") (pinfunction "2_2") (pintype "passive"))
      (node (ref "R33") (pin "2") (pinfunction "2_2") (pintype "passive"))
      (node (ref "R34") (pin "2") (pinfunction "2_2") (pintype "passive"))
      (node (ref "TP5") (pin "TP") (pinfunction "TP_TP") (pintype "input"))
    )
    (net (code "101") (name "VCC") (class "Default")
      (node (ref "C1") (pin "1") (pinfunction "1_1") (pintype "passive"))
      (node (ref "C15") (pin "1") (pinfunction "1_1") (pintype "passive"))
      (node (ref "C17") (pin "1") (pinfunction "1_1") (pintype "passive"))
      (node (ref "C18") (pin "1") (pinfunction "1_1") (pintype "passive"))
      (node (ref "C2") (pin "1") (pinfunction "1_1") (pintype "passive"))
      (node (ref "C24") (pin "1") (pinfunction "1_1") (pintype "passive"))
      (node (ref "C29") (pin "1") (pinfunction "1_1") (pintype "passive"))
      (node (ref "C3") (pin "+") (pinfunction "+_+") (pintype "passive"))
      (node (ref "C30") (pin "1") (pinfunction "1_1") (pintype "passive"))
      (node (ref "C31") (pin "1") (pinfunction "1_1") (pintype "passive"))
      (node (ref "C35") (pin "1") (pinfunction "1_1") (pintype "passive"))
      (node (ref "C36") (pin "1") (pinfunction "1_1") (pintype "passive"))
      (node (ref "C7") (pin "1") (pinfunction "1_1") (pintype "passive"))
      (node (ref "C8") (pin "1") (pinfunction "1_1") (pintype "passive"))
      (node (ref "C9") (pin "1") (pinfunction "1_1") (pintype "passive"))
      (node (ref "D3") (pin "A") (pinfunction "A_A") (pintype "passive"))
      (node (ref "EXP1") (pin "2") (pinfunction "S_2") (pintype "passive"))
      (node (ref "EXP1") (pin "25") (pinfunction "S_25") (pintype "passive"))
      (node (ref "F1") (pin "1") (pinfunction "1_1") (pintype "passive"))
      (node (ref "I2C") (pin "3") (pinfunction "3_3") (pintype "bidirectional"))
      (node (ref "IC1") (pin "1") (pinfunction "VDD_1") (pintype "bidirectional"))
      (node (ref "IC1") (pin "12") (pinfunction "VDD_2_12") (pintype "bidirectional"))
      (node (ref "IC1") (pin "35") (pinfunction "AVDD_35") (pintype "bidirectional"))
      (node (ref "IC1") (pin "36") (pinfunction "AVDD_2_36") (pintype "bidirectional"))
      (node (ref "IC3") (pin "8") (pinfunction "VCC_8") (pintype "bidirectional"))
      (node (ref "IC5") (pin "5") (pinfunction "V+_5") (pintype "power_in"))
      (node (ref "LED1") (pin "2") (pinfunction "VDD_2") (pintype "power_in"))
      (node (ref "MIC1") (pin "1") (pinfunction "VDD_1") (pintype "bidirectional"))
      (node (ref "Q1") (pin "2") (pinfunction "S_2") (pintype "passive"))
      (node (ref "Q4") (pin "2") (pinfunction "S_2") (pintype "passive"))
      (node (ref "R19") (pin "2") (pinfunction "2_2") (pintype "passive"))
      (node (ref "R2") (pin "2") (pinfunction "2_2") (pintype "passive"))
      (node (ref "R20") (pin "2") (pinfunction "2_2") (pintype "passive"))
      (node (ref "R25") (pin "2") (pinfunction "2_2") (pintype "passive"))
      (node (ref "R26") (pin "2") (pinfunction "2_2") (pintype "passive"))
      (node (ref "R3") (pin "2") (pinfunction "2_2") (pintype "passive"))
      (node (ref "R30") (pin "2") (pinfunction "2_2") (pintype "passive"))
      (node (ref "R37") (pin "2") (pinfunction "2_2") (pintype "passive"))
      (node (ref "R42") (pin "2") (pinfunction "2_2") (pintype "passive"))
      (node (ref "R48") (pin "2") (pinfunction "2_2") (pintype "passive"))
      (node (ref "R6") (pin "2") (pinfunction "2_2") (pintype "passive"))
      (node (ref "R7") (pin "2") (pinfunction "2_2") (pintype "passive"))
      (node (ref "SERIAL") (pin "3") (pinfunction "3_3") (pintype "bidirectional"))
      (node (ref "U1") (pin "13") (pinfunction "VDDIO_13") (pintype "bidirectional"))
      (node (ref "U1") (pin "3") (pinfunction "VDD_3") (pintype "bidirectional"))
      (node (ref "U1") (pin "7") (pinfunction "PS_7") (pintype "bidirectional"))
    )
    (net (code "102") (name "VM") (class "Default")
      (node (ref "C16") (pin "1") (pinfunction "1_1") (pintype "passive"))
      (node (ref "C26") (pin "1") (pinfunction "1_1") (pintype "passive"))
      (node (ref "D3") (pin "C") (pinfunction "C_C") (pintype "passive"))
      (node (ref "IC3") (pin "1") (pinfunction "VM_1") (pintype "bidirectional"))
      (node (ref "JP1") (pin "5") (pinfunction "5_5") (pintype "passive"))
    )
    (net (code "103") (name "unconnected-(IC1-DCC-Pad2)") (class "Default")
      (node (ref "IC1") (pin "2") (pinfunction "DCC_2") (pintype "bidirectional"))
    )
    (net (code "104") (name "unconnected-(IC4-PTA1-Pad11)") (class "Default")
      (node (ref "IC4") (pin "11") (pinfunction "PTA1_11") (pintype "bidirectional"))
    )
    (net (code "105") (name "unconnected-(IC4-PTA2-Pad12)") (class "Default")
      (node (ref "IC4") (pin "12") (pinfunction "PTA2_12") (pintype "bidirectional"))
    )
    (net (code "106") (name "unconnected-(IC4-PTE0-Pad1)") (class "Default")
      (node (ref "IC4") (pin "1") (pinfunction "PTE0_1") (pintype "bidirectional"))
    )
    (net (code "107") (name "unconnected-(IC4-PTE30-Pad9)") (class "Default")
      (node (ref "IC4") (pin "9") (pinfunction "PTE30_9") (pintype "bidirectional"))
    )
    (net (code "108") (name "unconnected-(LED1-DO-Pad3)") (class "Default")
      (node (ref "LED1") (pin "3") (pinfunction "DO_3") (pintype "output"))
    )
    (net (code "109") (name "unconnected-(U1-CSB1-Pad16)") (class "Default")
      (node (ref "U1") (pin "16") (pinfunction "CSB1_16") (pintype "bidirectional"))
    )
    (net (code "110") (name "unconnected-(U1-CSB2-Pad5)") (class "Default")
      (node (ref "U1") (pin "5") (pinfunction "CSB2_5") (pintype "bidirectional"))
    )
    (net (code "111") (name "unconnected-(U1-INT2-Pad1)") (class "Default")
      (node (ref "U1") (pin "1") (pinfunction "INT2_1") (pintype "bidirectional"))
    )
    (net (code "112") (name "unconnected-(U1-INT4-Pad15)") (class "Default")
      (node (ref "U1") (pin "15") (pinfunction "INT4_15") (pintype "bidirectional"))
    )
    (net (code "113") (name "unconnected-(U1-INT5-Pad10)") (class "Default")
      (node (ref "U1") (pin "10") (pinfunction "INT5_10") (pintype "bidirectional"))
    )
    (net (code "114") (name "unconnected-(U1-N{slash}C-Pad8)") (class "Default")
      (node (ref "U1") (pin "8") (pinfunction "N/C_8") (pintype "bidirectional"))
    )
    (net (code "115") (name "unconnected-(U1-N{slash}C-Pad18)") (class "Default")
      (node (ref "U1") (pin "18") (pinfunction "N/C_18") (pintype "bidirectional"))
    )
    (net (code "116") (name "unconnected-(USB2-Pad4)") (class "Default")
      (node (ref "USB2") (pin "4") (pinfunction "4_4") (pintype "bidirectional"))
    )
  )
)
